# bontor_mbed_lowpan_rev_f.net
KiCad netlist of a schematic drawn in EAGLE
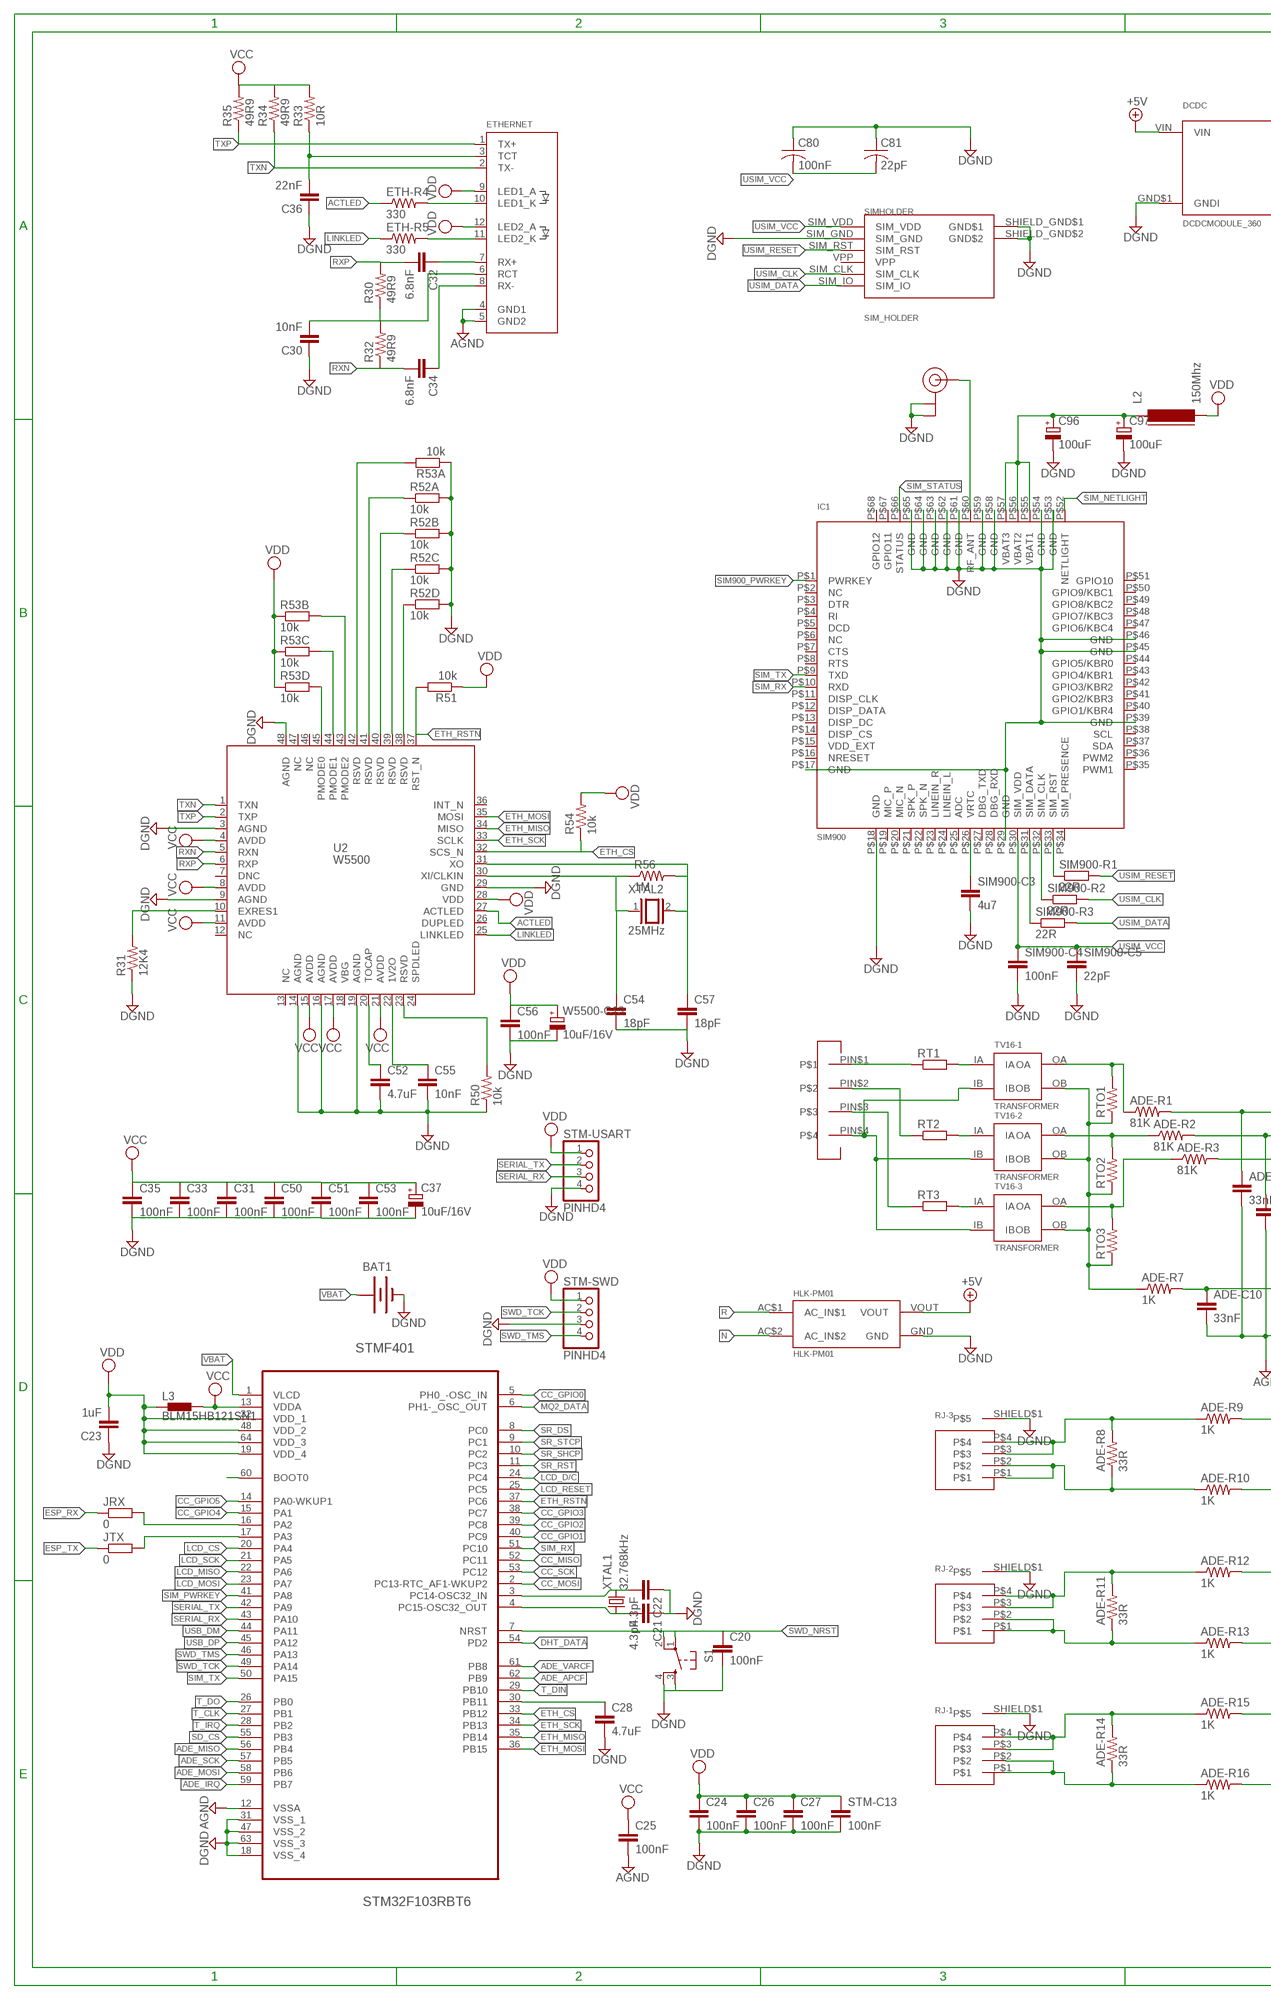
[diagram p0: schematic, sheet 1, part 1 of 2]
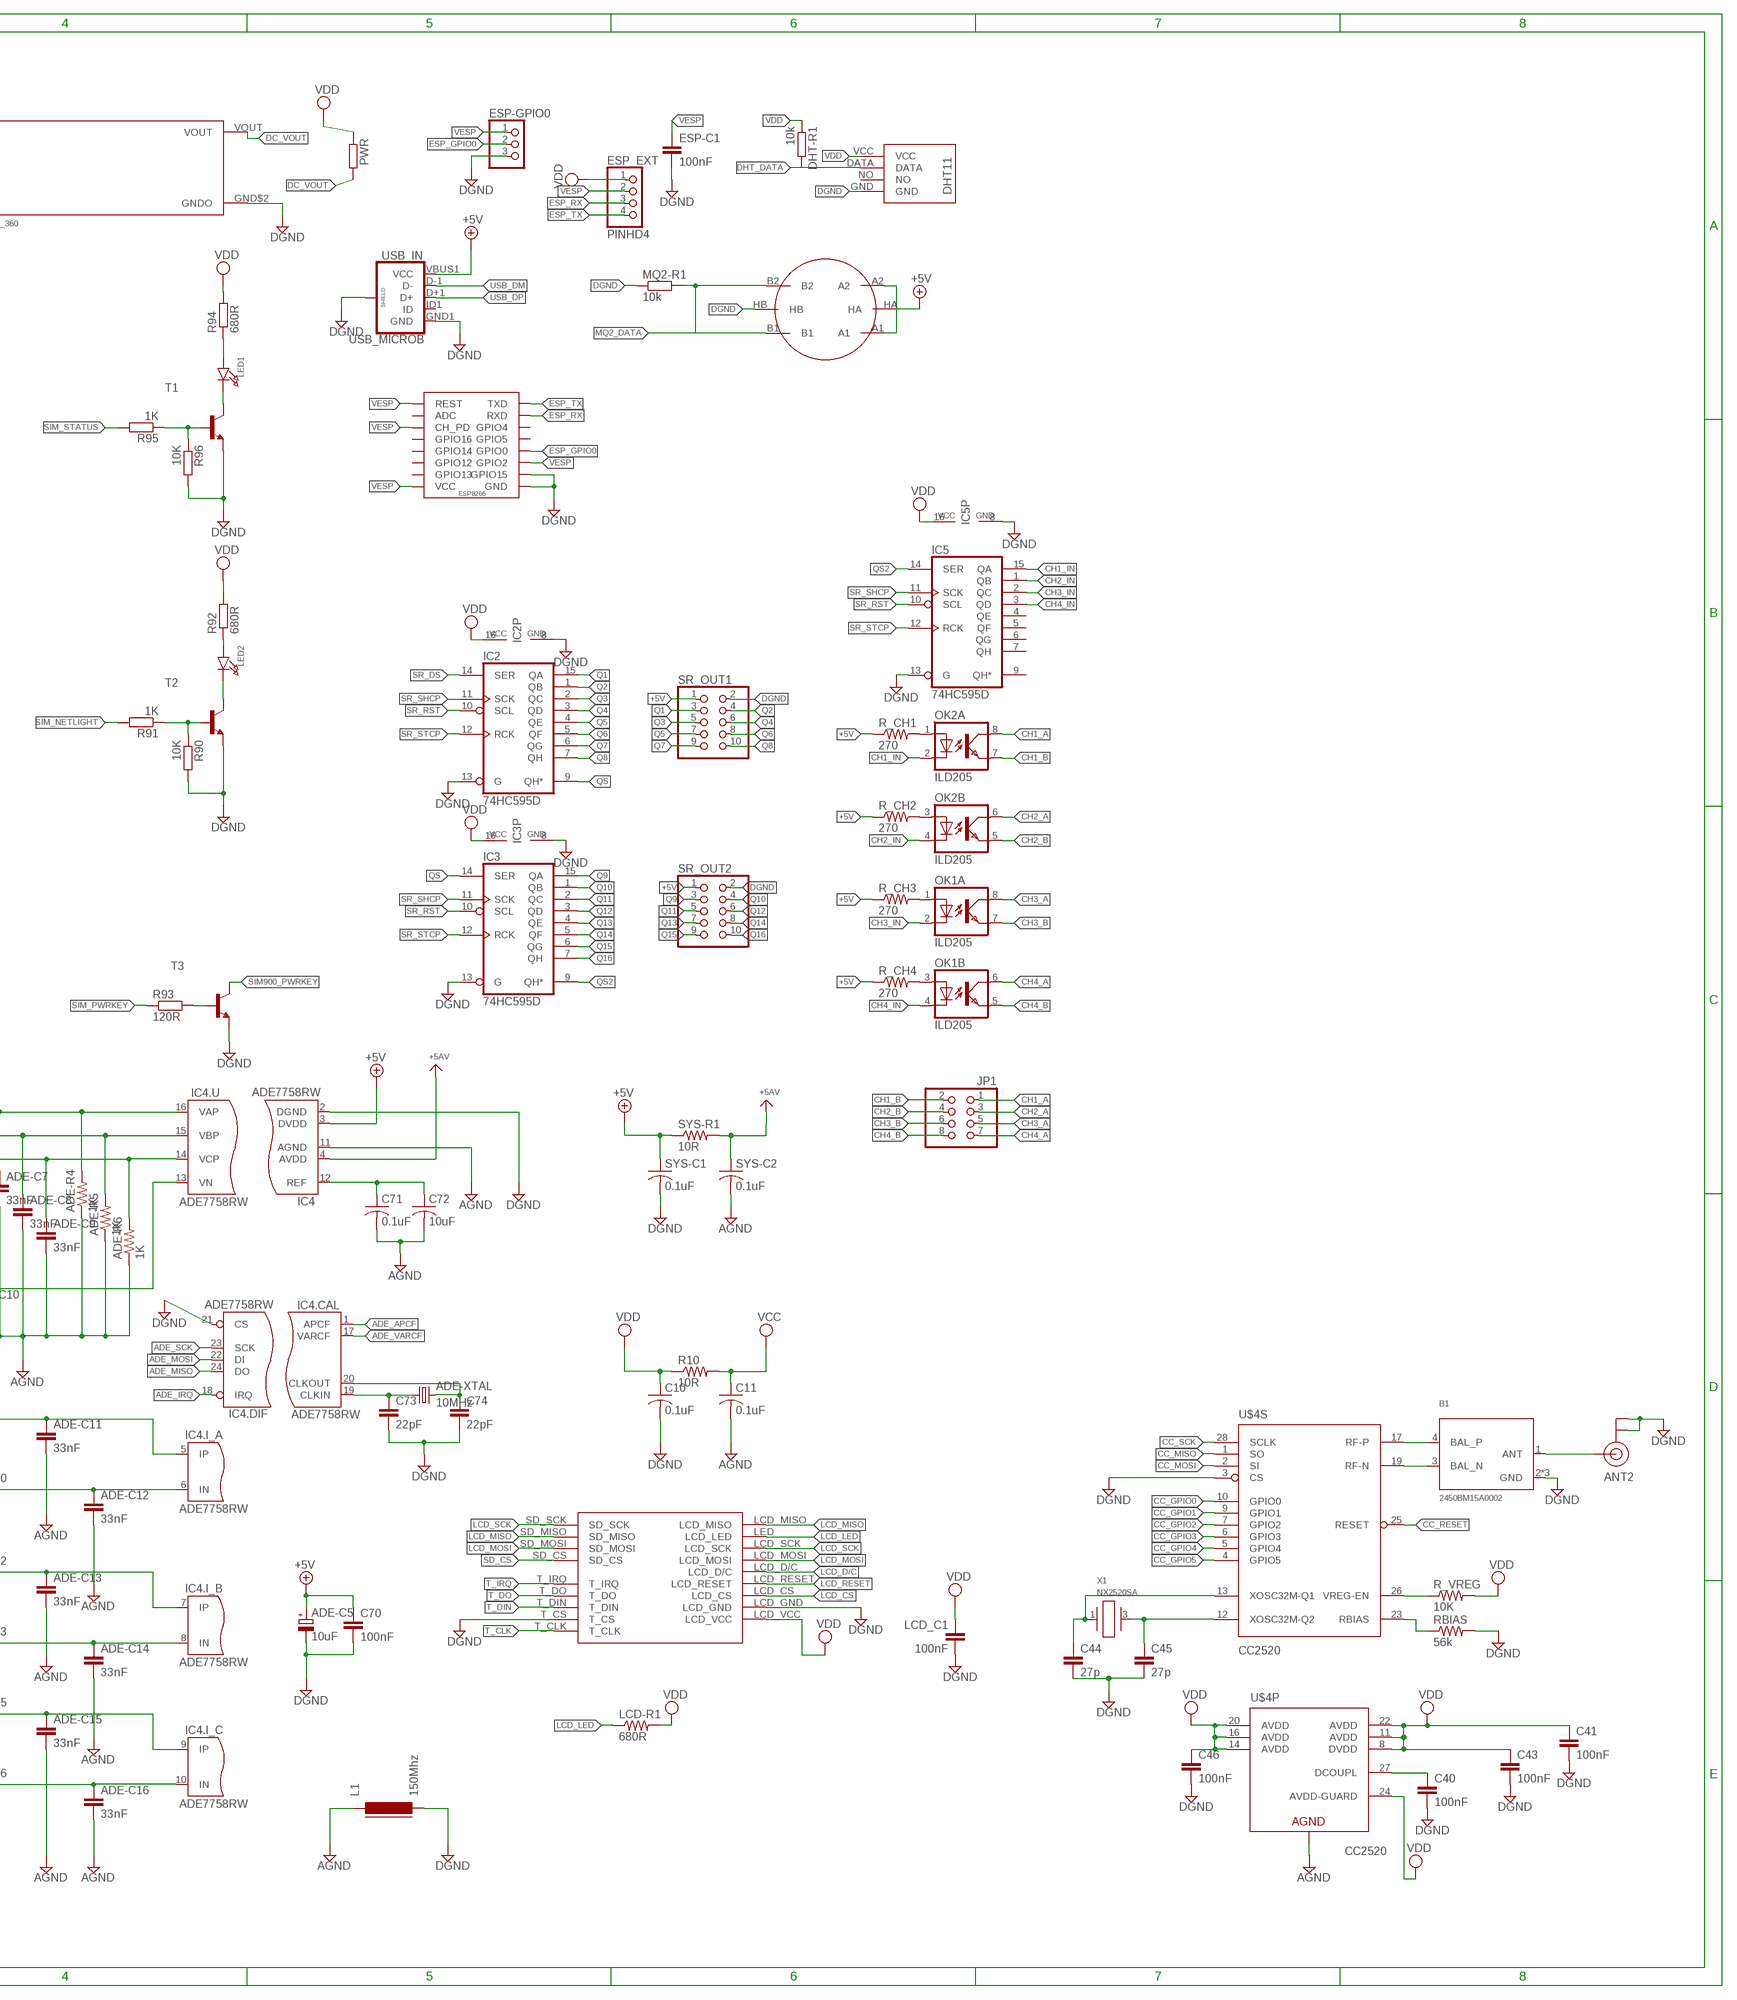
[diagram p1: schematic, sheet 1, part 2 of 2]

(export (version "E")
  (design (tool "Eeschema 10.0.6"))
  (components
    (comp (ref "ADE-C5")
      (value "10uF")
      (footprint "eagle-import:153CLV-0605")
      (libsource (lib "eagle-import") (part "CPOL-EU153CLV-0605"))
    )
    (comp (ref "ADE-C7")
      (value "33nF")
      (footprint "eagle-import:0603-CAP")
      (libsource (lib "eagle-import") (part "CAP0603-CAP"))
    )
    (comp (ref "ADE-C8")
      (value "33nF")
      (footprint "eagle-import:0603-CAP")
      (libsource (lib "eagle-import") (part "CAP0603-CAP"))
    )
    (comp (ref "ADE-C9")
      (value "33nF")
      (footprint "eagle-import:0603-CAP")
      (libsource (lib "eagle-import") (part "CAP0603-CAP"))
    )
    (comp (ref "ADE-C10")
      (value "33nF")
      (footprint "eagle-import:0603-CAP")
      (libsource (lib "eagle-import") (part "CAP0603-CAP"))
    )
    (comp (ref "ADE-C11")
      (value "33nF")
      (footprint "eagle-import:0402-CAP")
      (libsource (lib "eagle-import") (part "CAP0402-CAP"))
    )
    (comp (ref "ADE-C12")
      (value "33nF")
      (footprint "eagle-import:0402-CAP")
      (libsource (lib "eagle-import") (part "CAP0402-CAP"))
    )
    (comp (ref "ADE-C13")
      (value "33nF")
      (footprint "eagle-import:0402-CAP")
      (libsource (lib "eagle-import") (part "CAP0402-CAP"))
    )
    (comp (ref "ADE-C14")
      (value "33nF")
      (footprint "eagle-import:0402-CAP")
      (libsource (lib "eagle-import") (part "CAP0402-CAP"))
    )
    (comp (ref "ADE-C15")
      (value "33nF")
      (footprint "eagle-import:0402-CAP")
      (libsource (lib "eagle-import") (part "CAP0402-CAP"))
    )
    (comp (ref "ADE-C16")
      (value "33nF")
      (footprint "eagle-import:0402-CAP")
      (libsource (lib "eagle-import") (part "CAP0402-CAP"))
    )
    (comp (ref "ADE-R1")
      (value "81K")
      (footprint "eagle-import:0603-RES")
      (libsource (lib "eagle-import") (part "RESISTOR0603-RES"))
    )
    (comp (ref "ADE-R2")
      (value "81K")
      (footprint "eagle-import:0603-RES")
      (libsource (lib "eagle-import") (part "RESISTOR0603-RES"))
    )
    (comp (ref "ADE-R3")
      (value "81K")
      (footprint "eagle-import:0603-RES")
      (libsource (lib "eagle-import") (part "RESISTOR0603-RES"))
    )
    (comp (ref "ADE-R4")
      (value "1K")
      (footprint "eagle-import:0603-RES")
      (libsource (lib "eagle-import") (part "RESISTOR0603-RES"))
    )
    (comp (ref "ADE-R5")
      (value "1K")
      (footprint "eagle-import:0603-RES")
      (libsource (lib "eagle-import") (part "RESISTOR0603-RES"))
    )
    (comp (ref "ADE-R6")
      (value "1K")
      (footprint "eagle-import:0603-RES")
      (libsource (lib "eagle-import") (part "RESISTOR0603-RES"))
    )
    (comp (ref "ADE-R7")
      (value "1K")
      (footprint "eagle-import:0603-RES")
      (libsource (lib "eagle-import") (part "RESISTOR0603-RES"))
    )
    (comp (ref "ADE-R8")
      (value "33R")
      (footprint "eagle-import:0402-RES")
      (libsource (lib "eagle-import") (part "RESISTOR0402-RES"))
    )
    (comp (ref "ADE-R9")
      (value "1K")
      (footprint "eagle-import:0402-RES")
      (libsource (lib "eagle-import") (part "RESISTOR0402-RES"))
    )
    (comp (ref "ADE-R10")
      (value "1K")
      (footprint "eagle-import:0402-RES")
      (libsource (lib "eagle-import") (part "RESISTOR0402-RES"))
    )
    (comp (ref "ADE-R11")
      (value "33R")
      (footprint "eagle-import:0402-RES")
      (libsource (lib "eagle-import") (part "RESISTOR0402-RES"))
    )
    (comp (ref "ADE-R12")
      (value "1K")
      (footprint "eagle-import:0402-RES")
      (libsource (lib "eagle-import") (part "RESISTOR0402-RES"))
    )
    (comp (ref "ADE-R13")
      (value "1K")
      (footprint "eagle-import:0402-RES")
      (libsource (lib "eagle-import") (part "RESISTOR0402-RES"))
    )
    (comp (ref "ADE-R14")
      (value "33R")
      (footprint "eagle-import:0402-RES")
      (libsource (lib "eagle-import") (part "RESISTOR0402-RES"))
    )
    (comp (ref "ADE-R15")
      (value "1K")
      (footprint "eagle-import:0402-RES")
      (libsource (lib "eagle-import") (part "RESISTOR0402-RES"))
    )
    (comp (ref "ADE-R16")
      (value "1K")
      (footprint "eagle-import:0402-RES")
      (libsource (lib "eagle-import") (part "RESISTOR0402-RES"))
    )
    (comp (ref "ADE-XTAL")
      (value "10MHz")
      (footprint "eagle-import:HC49US")
      (libsource (lib "eagle-import") (part "CRYSTALHC49US"))
    )
    (comp (ref "ANT1")
      (value "U.FL")
      (footprint "eagle-import:U.FL")
      (libsource (lib "eagle-import") (part "U.FL"))
    )
    (comp (ref "ANT2")
      (value "U.FL")
      (footprint "eagle-import:U.FL")
      (libsource (lib "eagle-import") (part "SparkFun-Connectors_U.FL"))
    )
    (comp (ref "B1")
      (value "2450BM15A0002")
      (footprint "eagle-import:2450BM")
      (libsource (lib "eagle-import") (part "2450BM15A0002"))
    )
    (comp (ref "BAT1")
      (value "BATTERY12MM")
      (footprint "eagle-import:BATTCON_12MM")
      (libsource (lib "eagle-import") (part "BATTERY12MM"))
    )
    (comp (ref "C10")
      (value "0.1uF")
      (footprint "eagle-import:C0603@1")
      (libsource (lib "eagle-import") (part "C-USC0603"))
    )
    (comp (ref "C11")
      (value "0.1uF")
      (footprint "eagle-import:C0603@1")
      (libsource (lib "eagle-import") (part "C-USC0603"))
    )
    (comp (ref "C20")
      (value "100nF")
      (footprint "eagle-import:C0603")
      (libsource (lib "eagle-import") (part "C-EUC0603"))
    )
    (comp (ref "C21")
      (value "4.3pF")
      (footprint "eagle-import:C0603")
      (libsource (lib "eagle-import") (part "C-EUC0603"))
    )
    (comp (ref "C22")
      (value "4.3pF")
      (footprint "eagle-import:C0603")
      (libsource (lib "eagle-import") (part "C-EUC0603"))
    )
    (comp (ref "C23")
      (value "1uF")
      (footprint "eagle-import:C0603")
      (libsource (lib "eagle-import") (part "C-EUC0603"))
    )
    (comp (ref "C24")
      (value "100nF")
      (footprint "eagle-import:C0603")
      (libsource (lib "eagle-import") (part "C-EUC0603"))
    )
    (comp (ref "C25")
      (value "100nF")
      (footprint "eagle-import:C0603")
      (libsource (lib "eagle-import") (part "C-EUC0603"))
    )
    (comp (ref "C26")
      (value "100nF")
      (footprint "eagle-import:C0603")
      (libsource (lib "eagle-import") (part "C-EUC0603"))
    )
    (comp (ref "C27")
      (value "100nF")
      (footprint "eagle-import:C0402")
      (libsource (lib "eagle-import") (part "C-EUC0402"))
    )
    (comp (ref "C28")
      (value "4.7uF")
      (footprint "eagle-import:C0603")
      (libsource (lib "eagle-import") (part "C-EUC0603"))
    )
    (comp (ref "C30")
      (value "10nF")
      (footprint "eagle-import:C0603")
      (libsource (lib "eagle-import") (part "C-EUC0603"))
    )
    (comp (ref "C31")
      (value "100nF")
      (footprint "eagle-import:C0603")
      (libsource (lib "eagle-import") (part "C-EUC0603"))
    )
    (comp (ref "C32")
      (value "6.8nF")
      (footprint "eagle-import:C0603")
      (libsource (lib "eagle-import") (part "C-EUC0603"))
    )
    (comp (ref "C33")
      (value "100nF")
      (footprint "eagle-import:C0603")
      (libsource (lib "eagle-import") (part "C-EUC0603"))
    )
    (comp (ref "C34")
      (value "6.8nF")
      (footprint "eagle-import:C0603")
      (libsource (lib "eagle-import") (part "C-EUC0603"))
    )
    (comp (ref "C35")
      (value "100nF")
      (footprint "eagle-import:C0603")
      (libsource (lib "eagle-import") (part "C-EUC0603"))
    )
    (comp (ref "C36")
      (value "22nF")
      (footprint "eagle-import:C0603")
      (libsource (lib "eagle-import") (part "C-EUC0603"))
    )
    (comp (ref "C37")
      (value "10uF/16V")
      (footprint "eagle-import:153CLV-0605")
      (libsource (lib "eagle-import") (part "CPOL-EU153CLV-0605"))
    )
    (comp (ref "C40")
      (value "100nF")
      (footprint "eagle-import:C0402")
      (libsource (lib "eagle-import") (part "C-EUC0402"))
    )
    (comp (ref "C41")
      (value "100nF")
      (footprint "eagle-import:C0402")
      (libsource (lib "eagle-import") (part "C-EUC0402"))
    )
    (comp (ref "C43")
      (value "100nF")
      (footprint "eagle-import:C0402")
      (libsource (lib "eagle-import") (part "C-EUC0402"))
    )
    (comp (ref "C44")
      (value "27p")
      (footprint "eagle-import:C0201")
      (libsource (lib "eagle-import") (part "C-EUC0201"))
    )
    (comp (ref "C45")
      (value "27p")
      (footprint "eagle-import:C0201")
      (libsource (lib "eagle-import") (part "C-EUC0201"))
    )
    (comp (ref "C46")
      (value "100nF")
      (footprint "eagle-import:C0402")
      (libsource (lib "eagle-import") (part "C-EUC0402"))
    )
    (comp (ref "C50")
      (value "100nF")
      (footprint "eagle-import:C0603")
      (libsource (lib "eagle-import") (part "C-EUC0603"))
    )
    (comp (ref "C51")
      (value "100nF")
      (footprint "eagle-import:C0603")
      (libsource (lib "eagle-import") (part "C-EUC0603"))
    )
    (comp (ref "C52")
      (value "4.7uF")
      (footprint "eagle-import:C0603")
      (libsource (lib "eagle-import") (part "C-EUC0603"))
    )
    (comp (ref "C53")
      (value "100nF")
      (footprint "eagle-import:C0603")
      (libsource (lib "eagle-import") (part "C-EUC0603"))
    )
    (comp (ref "C54")
      (value "18pF")
      (footprint "eagle-import:C0603")
      (libsource (lib "eagle-import") (part "C-EUC0603"))
    )
    (comp (ref "C55")
      (value "10nF")
      (footprint "eagle-import:C0603")
      (libsource (lib "eagle-import") (part "C-EUC0603"))
    )
    (comp (ref "C56")
      (value "100nF")
      (footprint "eagle-import:C0603")
      (libsource (lib "eagle-import") (part "C-EUC0603"))
    )
    (comp (ref "C57")
      (value "18pF")
      (footprint "eagle-import:C0603")
      (libsource (lib "eagle-import") (part "C-EUC0603"))
    )
    (comp (ref "C70")
      (value "100nF")
      (footprint "eagle-import:C0603")
      (libsource (lib "eagle-import") (part "C-EUC0603"))
    )
    (comp (ref "C71")
      (value "0.1uF")
      (footprint "eagle-import:C0603@1")
      (libsource (lib "eagle-import") (part "C-USC0603"))
    )
    (comp (ref "C72")
      (value "10uF")
      (footprint "eagle-import:C0805K")
      (libsource (lib "eagle-import") (part "C-USC0805K"))
    )
    (comp (ref "C73")
      (value "22pF")
      (footprint "eagle-import:C0603")
      (libsource (lib "eagle-import") (part "C-EUC0603"))
    )
    (comp (ref "C74")
      (value "22pF")
      (footprint "eagle-import:C0603")
      (libsource (lib "eagle-import") (part "C-EUC0603"))
    )
    (comp (ref "C80")
      (value "100nF")
      (footprint "eagle-import:C0603K")
      (libsource (lib "eagle-import") (part "C-USC0603K"))
    )
    (comp (ref "C81")
      (value "22pF")
      (footprint "eagle-import:C0603K")
      (libsource (lib "eagle-import") (part "C-USC0603K"))
    )
    (comp (ref "C96")
      (value "100uF")
      (footprint "eagle-import:153CLV-0605")
      (libsource (lib "eagle-import") (part "CPOL-EU153CLV-0605"))
    )
    (comp (ref "C97")
      (value "100uF")
      (footprint "eagle-import:153CLV-0605")
      (libsource (lib "eagle-import") (part "CPOL-EU153CLV-0605"))
    )
    (comp (ref "DCDC")
      (value "DCDCMODULE_360")
      (footprint "eagle-import:DCDCMODULE-360")
      (libsource (lib "eagle-import") (part "DCDCMODULE_360"))
    )
    (comp (ref "DHT-R1")
      (value "10k")
      (footprint "eagle-import:R0603")
      (libsource (lib "eagle-import") (part "resistor_R-EU_R0603"))
    )
    (comp (ref "ESP")
      (value "ESP")
      (footprint "eagle-import:WI12")
      (libsource (lib "eagle-import") (part "ESP8266WI12"))
    )
    (comp (ref "ESP-C1")
      (value "100nF")
      (footprint "eagle-import:C0603")
      (libsource (lib "eagle-import") (part "C-EUC0603"))
    )
    (comp (ref "ESP-GPIO0")
      (value "PINHD-1X3")
      (footprint "eagle-import:1X03")
      (libsource (lib "eagle-import") (part "PINHD-1X3"))
    )
    (comp (ref "ESP_EXT")
      (value "PINHD4")
      (footprint "eagle-import:PINHD4")
      (libsource (lib "eagle-import") (part "PINHD4"))
    )
    (comp (ref "ETH-R4")
      (value "330")
      (footprint "eagle-import:R0603")
      (libsource (lib "eagle-import") (part "resistor_R-US_R0603"))
    )
    (comp (ref "ETH-R5")
      (value "330")
      (footprint "eagle-import:R0603")
      (libsource (lib "eagle-import") (part "resistor_R-US_R0603"))
    )
    (comp (ref "ETHERNET")
      (value "RJ45J0026D21BNL")
      (footprint "eagle-import:RJ45_PULSEJACK")
      (libsource (lib "eagle-import") (part "RJ45J0026D21BNL"))
    )
    (comp (ref "HLK-PM01")
      (value "HLK-PM01")
      (footprint "eagle-import:HLK-PM01")
      (libsource (lib "eagle-import") (part "HLK-PM01"))
    )
    (comp (ref "IC1")
      (value "SIM900")
      (footprint "eagle-import:SIM900_SMT")
      (libsource (lib "eagle-import") (part "GSM_SIM900_LITERAL"))
    )
    (comp (ref "IC2")
      (value "74HC595D")
      (footprint "eagle-import:SO16")
      (libsource (lib "eagle-import") (part "74595DHC"))
    )
    (comp (ref "IC3")
      (value "74HC595D")
      (footprint "eagle-import:SO16")
      (libsource (lib "eagle-import") (part "74595DHC"))
    )
    (comp (ref "IC4")
      (value "ADE7758RW")
      (footprint "eagle-import:SOIC24")
      (libsource (lib "eagle-import") (part "ADE7758RW"))
    )
    (comp (ref "IC5")
      (value "74HC595D")
      (footprint "eagle-import:SO16")
      (libsource (lib "eagle-import") (part "74595DHC"))
    )
    (comp (ref "JP1")
      (value "PINHD-2X4")
      (footprint "eagle-import:2X04")
      (libsource (lib "eagle-import") (part "PINHD-2X4"))
    )
    (comp (ref "JRX")
      (value "0")
      (footprint "eagle-import:R0201")
      (libsource (lib "eagle-import") (part "R-EU_R0201"))
    )
    (comp (ref "JTX")
      (value "0")
      (footprint "eagle-import:R0201")
      (libsource (lib "eagle-import") (part "R-EU_R0201"))
    )
    (comp (ref "L1")
      (value "150Mhz")
      (footprint "eagle-import:FB805")
      (libsource (lib "eagle-import") (part "FERRITE-0805"))
    )
    (comp (ref "L2")
      (value "150Mhz")
      (footprint "eagle-import:FB805")
      (libsource (lib "eagle-import") (part "FERRITE-0805"))
    )
    (comp (ref "L3")
      (value "BLM15HB121SN1")
      (footprint "eagle-import:0402")
      (libsource (lib "eagle-import") (part "BLM15HB121SN1"))
    )
    (comp (ref "LCD-R1")
      (value "680R")
      (footprint "eagle-import:0603-RES")
      (libsource (lib "eagle-import") (part "RESISTOR0603-RES"))
    )
    (comp (ref "LCD14")
      (value "LCD_2.4")
      (footprint "eagle-import:LCD_TOUCH_2-4")
      (libsource (lib "eagle-import") (part "LCD_2.4"))
    )
    (comp (ref "LCD_C1")
      (value "100nF")
      (footprint "eagle-import:C0603")
      (libsource (lib "eagle-import") (part "C-EUC0603"))
    )
    (comp (ref "LED1")
      (value "LED0805_NOOUTLINE")
      (footprint "eagle-import:CHIPLED_0805_NOOUTLINE")
      (libsource (lib "eagle-import") (part "LED0805_NOOUTLINE"))
    )
    (comp (ref "LED2")
      (value "LED0805_NOOUTLINE")
      (footprint "eagle-import:CHIPLED_0805_NOOUTLINE")
      (libsource (lib "eagle-import") (part "LED0805_NOOUTLINE"))
    )
    (comp (ref "MQ2-R1")
      (value "10k")
      (footprint "eagle-import:R0603")
      (libsource (lib "eagle-import") (part "resistor_R-EU_R0603"))
    )
    (comp (ref "OK1")
      (value "ILD205")
      (footprint "eagle-import:SOIC08")
      (fields (field (name "MF") "VISHAY/TELEFUNKEN") (field (name "MPN") "ILD205T"))
      (libsource (lib "eagle-import") (part "ILD205"))
    )
    (comp (ref "OK2")
      (value "ILD205")
      (footprint "eagle-import:SOIC08")
      (fields (field (name "MF") "VISHAY/TELEFUNKEN") (field (name "MPN") "ILD205T"))
      (libsource (lib "eagle-import") (part "ILD205"))
    )
    (comp (ref "PWR")
      (value "R-EU_R0402")
      (footprint "eagle-import:R0402")
      (libsource (lib "eagle-import") (part "R-EU_R0402"))
    )
    (comp (ref "R10")
      (value "10R")
      (footprint "eagle-import:0603-RES")
      (libsource (lib "eagle-import") (part "RESISTOR0603-RES"))
    )
    (comp (ref "R30")
      (value "49R9")
      (footprint "eagle-import:R0603")
      (libsource (lib "eagle-import") (part "resistor_R-US_R0603"))
    )
    (comp (ref "R31")
      (value "12K4")
      (footprint "eagle-import:R0805")
      (libsource (lib "eagle-import") (part "resistor_R-US_R0805"))
    )
    (comp (ref "R32")
      (value "49R9")
      (footprint "eagle-import:R0603")
      (libsource (lib "eagle-import") (part "resistor_R-US_R0603"))
    )
    (comp (ref "R33")
      (value "10R")
      (footprint "eagle-import:R0603")
      (libsource (lib "eagle-import") (part "resistor_R-US_R0603"))
    )
    (comp (ref "R34")
      (value "49R9")
      (footprint "eagle-import:R0603")
      (libsource (lib "eagle-import") (part "resistor_R-US_R0603"))
    )
    (comp (ref "R35")
      (value "49R9")
      (footprint "eagle-import:R0603")
      (libsource (lib "eagle-import") (part "resistor_R-US_R0603"))
    )
    (comp (ref "R50")
      (value "10k")
      (footprint "eagle-import:R0603")
      (libsource (lib "eagle-import") (part "resistor_R-US_R0603"))
    )
    (comp (ref "R51")
      (value "10k")
      (footprint "eagle-import:R0603")
      (libsource (lib "eagle-import") (part "R-EU_R0603"))
    )
    (comp (ref "R52")
      (value "10k")
      (footprint "eagle-import:RN8P-4R-CRA06S")
      (libsource (lib "eagle-import") (part "RESISTOR_ARRAY_4"))
    )
    (comp (ref "R53")
      (value "10k")
      (footprint "eagle-import:RN8P-4R-CRA06S")
      (libsource (lib "eagle-import") (part "RESISTOR_ARRAY_4"))
    )
    (comp (ref "R54")
      (value "10k")
      (footprint "eagle-import:R0603")
      (libsource (lib "eagle-import") (part "resistor_R-US_R0603"))
    )
    (comp (ref "R56")
      (value "1M")
      (footprint "eagle-import:R0603")
      (libsource (lib "eagle-import") (part "resistor_R-US_R0603"))
    )
    (comp (ref "R90")
      (value "10K")
      (footprint "eagle-import:R0603")
      (libsource (lib "eagle-import") (part "R-EU_R0603"))
    )
    (comp (ref "R91")
      (value "1K")
      (footprint "eagle-import:R0603")
      (libsource (lib "eagle-import") (part "R-EU_R0603"))
    )
    (comp (ref "R92")
      (value "680R")
      (footprint "eagle-import:R0603")
      (libsource (lib "eagle-import") (part "R-EU_R0603"))
    )
    (comp (ref "R93")
      (value "120R")
      (footprint "eagle-import:R0603")
      (libsource (lib "eagle-import") (part "resistor_R-EU_R0603"))
    )
    (comp (ref "R94")
      (value "680R")
      (footprint "eagle-import:R0603")
      (libsource (lib "eagle-import") (part "R-EU_R0603"))
    )
    (comp (ref "R95")
      (value "1K")
      (footprint "eagle-import:R0603")
      (libsource (lib "eagle-import") (part "R-EU_R0603"))
    )
    (comp (ref "R96")
      (value "10K")
      (footprint "eagle-import:R0603")
      (libsource (lib "eagle-import") (part "R-EU_R0603"))
    )
    (comp (ref "RBIAS")
      (value "56k")
      (footprint "eagle-import:0402-RES")
      (libsource (lib "eagle-import") (part "RESISTOR0402-RES"))
    )
    (comp (ref "RJ-1")
      (value "RJ11-4P-V")
      (footprint "eagle-import:RJ11-4P-V")
      (libsource (lib "eagle-import") (part "RJ11-4P-V"))
    )
    (comp (ref "RJ-2")
      (value "RJ11-4P-V")
      (footprint "eagle-import:RJ11-4P-V")
      (libsource (lib "eagle-import") (part "RJ11-4P-V"))
    )
    (comp (ref "RJ-3")
      (value "RJ11-4P-V")
      (footprint "eagle-import:RJ11-4P-V")
      (libsource (lib "eagle-import") (part "RJ11-4P-V"))
    )
    (comp (ref "RT1")
      (value "R-EU_0309/V")
      (footprint "eagle-import:0309V")
      (libsource (lib "eagle-import") (part "R-EU_0309/V"))
    )
    (comp (ref "RT2")
      (value "R-EU_0309/V")
      (footprint "eagle-import:0309V")
      (libsource (lib "eagle-import") (part "R-EU_0309/V"))
    )
    (comp (ref "RT3")
      (value "R-EU_0309/V")
      (footprint "eagle-import:0309V")
      (libsource (lib "eagle-import") (part "R-EU_0309/V"))
    )
    (comp (ref "RTO1")
      (value "R-US_0309_12")
      (footprint "eagle-import:0309_12")
      (libsource (lib "eagle-import") (part "R-US_0309_12"))
    )
    (comp (ref "RTO2")
      (value "R-US_0309_12")
      (footprint "eagle-import:0309_12")
      (libsource (lib "eagle-import") (part "R-US_0309_12"))
    )
    (comp (ref "RTO3")
      (value "R-US_0309_12")
      (footprint "eagle-import:0309_12")
      (libsource (lib "eagle-import") (part "R-US_0309_12"))
    )
    (comp (ref "R_CH1")
      (value "270")
      (footprint "eagle-import:0603-RES")
      (libsource (lib "eagle-import") (part "RESISTOR0603-RES"))
    )
    (comp (ref "R_CH2")
      (value "270")
      (footprint "eagle-import:0603-RES")
      (libsource (lib "eagle-import") (part "RESISTOR0603-RES"))
    )
    (comp (ref "R_CH3")
      (value "270")
      (footprint "eagle-import:0603-RES")
      (libsource (lib "eagle-import") (part "RESISTOR0603-RES"))
    )
    (comp (ref "R_CH4")
      (value "270")
      (footprint "eagle-import:0603-RES")
      (libsource (lib "eagle-import") (part "RESISTOR0603-RES"))
    )
    (comp (ref "R_VREG")
      (value "10K")
      (footprint "eagle-import:0402-RES")
      (libsource (lib "eagle-import") (part "RESISTOR0402-RES"))
    )
    (comp (ref "S1")
      (value "TAC_SWITCHPTH")
      (footprint "eagle-import:TACTILE-PTH")
      (libsource (lib "eagle-import") (part "TAC_SWITCHPTH"))
    )
    (comp (ref "SENSOR-MQ2")
      (value "METHANE_SENSOR")
      (footprint "eagle-import:MQ-3")
      (libsource (lib "eagle-import") (part "METHANE_SENSOR"))
    )
    (comp (ref "SIM900-C3")
      (value "4u7")
      (footprint "eagle-import:C0603")
      (libsource (lib "eagle-import") (part "C-EUC0603"))
    )
    (comp (ref "SIM900-C4")
      (value "100nF")
      (footprint "eagle-import:C0603")
      (libsource (lib "eagle-import") (part "C-EUC0603"))
    )
    (comp (ref "SIM900-C5")
      (value "22pF")
      (footprint "eagle-import:C0603")
      (libsource (lib "eagle-import") (part "C-EUC0603"))
    )
    (comp (ref "SIM900-R1")
      (value "22R")
      (footprint "eagle-import:R0603")
      (libsource (lib "eagle-import") (part "R-EU_R0603"))
    )
    (comp (ref "SIM900-R2")
      (value "22R")
      (footprint "eagle-import:R0603")
      (libsource (lib "eagle-import") (part "R-EU_R0603"))
    )
    (comp (ref "SIM900-R3")
      (value "22R")
      (footprint "eagle-import:R0603")
      (libsource (lib "eagle-import") (part "R-EU_R0603"))
    )
    (comp (ref "SIMHOLDER")
      (value "SIM_HOLDER")
      (footprint "eagle-import:SIMHOLDER-PUSHPUSH")
      (libsource (lib "eagle-import") (part "SIM_HOLDER"))
    )
    (comp (ref "SR_OUT1")
      (value "PINHD-2X5")
      (footprint "eagle-import:2X05")
      (libsource (lib "eagle-import") (part "PINHD-2X5"))
    )
    (comp (ref "SR_OUT2")
      (value "PINHD-2X5")
      (footprint "eagle-import:2X05")
      (libsource (lib "eagle-import") (part "PINHD-2X5"))
    )
    (comp (ref "STM-C13")
      (value "100nF")
      (footprint "eagle-import:C0603")
      (libsource (lib "eagle-import") (part "C-EUC0603"))
    )
    (comp (ref "STM-SWD")
      (value "PINHD4")
      (footprint "eagle-import:PINHD4")
      (libsource (lib "eagle-import") (part "PINHD4"))
    )
    (comp (ref "STM-USART")
      (value "PINHD4")
      (footprint "eagle-import:PINHD4")
      (libsource (lib "eagle-import") (part "PINHD4"))
    )
    (comp (ref "STMF401")
      (value "STM32F103RBT6")
      (footprint "eagle-import:QFP50P1200X1200X160-64N")
      (fields (field (name "MPN") "STM32L152RBT6"))
      (libsource (lib "eagle-import") (part "STM32L152RBT6"))
    )
    (comp (ref "SYS-C1")
      (value "0.1uF")
      (footprint "eagle-import:C0603@1")
      (libsource (lib "eagle-import") (part "C-USC0603"))
    )
    (comp (ref "SYS-C2")
      (value "0.1uF")
      (footprint "eagle-import:C0603@1")
      (libsource (lib "eagle-import") (part "C-USC0603"))
    )
    (comp (ref "SYS-R1")
      (value "10R")
      (footprint "eagle-import:0603-RES")
      (libsource (lib "eagle-import") (part "RESISTOR0603-RES"))
    )
    (comp (ref "T1")
      (value "MMBT2222ALT1-NPN-SOT23-BEC")
      (footprint "eagle-import:SOT23-BEC")
      (libsource (lib "eagle-import") (part "-NPN-SOT23-BECMMBT2222ALT1"))
    )
    (comp (ref "T2")
      (value "MMBT2222ALT1-NPN-SOT23-BEC")
      (footprint "eagle-import:SOT23-BEC")
      (libsource (lib "eagle-import") (part "-NPN-SOT23-BECMMBT2222ALT1"))
    )
    (comp (ref "T3")
      (value "MMBT2222ALT1-NPN-SOT23-BEC")
      (footprint "eagle-import:SOT23-BEC")
      (libsource (lib "eagle-import") (part "transistor-neu-to92_-NPN-SOT23-BECMMBT2222ALT1"))
    )
    (comp (ref "TERM_BLOCK")
      (value "TERMINAL_BLOCK_TW")
      (footprint "eagle-import:TERMINAL-TWO-WAY")
      (libsource (lib "eagle-import") (part "TERMINAL_BLOCK_TW"))
    )
    (comp (ref "TV16-1")
      (value "TRANSFORMER")
      (footprint "eagle-import:TV16")
      (libsource (lib "eagle-import") (part "TRANSFORMER"))
    )
    (comp (ref "TV16-2")
      (value "TRANSFORMER")
      (footprint "eagle-import:TV16")
      (libsource (lib "eagle-import") (part "TRANSFORMER"))
    )
    (comp (ref "TV16-3")
      (value "TRANSFORMER")
      (footprint "eagle-import:TV16")
      (libsource (lib "eagle-import") (part "TRANSFORMER"))
    )
    (comp (ref "U$4")
      (value "CC2520")
      (footprint "eagle-import:QFN50P500X500X100-29N")
      (libsource (lib "eagle-import") (part "CC2520"))
    )
    (comp (ref "U$17")
      (value "DHT11")
      (footprint "eagle-import:DHT11")
      (libsource (lib "eagle-import") (part "DHT11"))
    )
    (comp (ref "U2")
      (value "W5500")
      (footprint "eagle-import:W5500")
      (libsource (lib "eagle-import") (part "W5500"))
    )
    (comp (ref "USB_IN")
      (value "USB_MICROB")
      (footprint "eagle-import:USB-B-MICRO-SMD_V03")
      (libsource (lib "eagle-import") (part "USB_MICROB_PLUGCONN-11752"))
    )
    (comp (ref "W5500-C13")
      (value "10uF/16V")
      (footprint "eagle-import:153CLV-0605")
      (libsource (lib "eagle-import") (part "CPOL-EU153CLV-0605"))
    )
    (comp (ref "X1")
      (value "NX2520SA")
      (footprint "eagle-import:NX2520SA")
      (libsource (lib "eagle-import") (part "NX2520SA"))
    )
    (comp (ref "XTAL1")
      (value "32.768kHz")
      (footprint "eagle-import:TC26H")
      (libsource (lib "eagle-import") (part "CRYSTALTC26H"))
    )
    (comp (ref "XTAL2")
      (value "25MHz")
      (footprint "eagle-import:QS")
      (libsource (lib "eagle-import") (part "XTAL/S"))
    )
  )
  (nets
    (net (code "1") (name "+5AV") (class "Default")
      (node (ref "IC4") (pin "4") (pinfunction "AVDD_4") (pintype "power_in"))
      (node (ref "SYS-C2") (pin "1") (pinfunction "1_1") (pintype "passive"))
      (node (ref "SYS-R1") (pin "2") (pinfunction "2_2") (pintype "passive"))
    )
    (net (code "2") (name "+5V") (class "Default")
      (node (ref "ADE-C5") (pin "+") (pinfunction "+_+") (pintype "passive"))
      (node (ref "C70") (pin "1") (pinfunction "1_1") (pintype "passive"))
      (node (ref "DCDC") (pin "VIN") (pinfunction "VIN_VIN") (pintype "bidirectional"))
      (node (ref "HLK-PM01") (pin "VOUT") (pinfunction "VOUT_VOUT") (pintype "bidirectional"))
      (node (ref "IC4") (pin "3") (pinfunction "DVDD_3") (pintype "power_in"))
      (node (ref "R_CH1") (pin "1") (pinfunction "1_1") (pintype "passive"))
      (node (ref "R_CH2") (pin "1") (pinfunction "1_1") (pintype "passive"))
      (node (ref "R_CH3") (pin "1") (pinfunction "1_1") (pintype "passive"))
      (node (ref "R_CH4") (pin "1") (pinfunction "1_1") (pintype "passive"))
      (node (ref "SENSOR-MQ2") (pin "A1") (pinfunction "A1_A1") (pintype "bidirectional"))
      (node (ref "SENSOR-MQ2") (pin "A2") (pinfunction "A2_A2") (pintype "bidirectional"))
      (node (ref "SENSOR-MQ2") (pin "HA") (pinfunction "HA_HA") (pintype "bidirectional"))
      (node (ref "SR_OUT1") (pin "1") (pinfunction "1_1") (pintype "passive"))
      (node (ref "SR_OUT2") (pin "1") (pinfunction "1_1") (pintype "passive"))
      (node (ref "SYS-C1") (pin "1") (pinfunction "1_1") (pintype "passive"))
      (node (ref "SYS-R1") (pin "1") (pinfunction "1_1") (pintype "passive"))
      (node (ref "USB_IN") (pin "VBUS1") (pinfunction "VCC_VBUS1") (pintype "bidirectional"))
    )
    (net (code "3") (name "/GPIO11") (class "Default")
      (node (ref "IC1") (pin "P$67") (pinfunction "GPIO11_P$67") (pintype "power_in"))
    )
    (net (code "4") (name "/GPIO12") (class "Default")
      (node (ref "IC1") (pin "P$68") (pinfunction "GPIO12_P$68") (pintype "power_in"))
    )
    (net (code "5") (name "ACTLED") (class "Default")
      (node (ref "ETH-R4") (pin "1") (pinfunction "1_1") (pintype "passive"))
      (node (ref "U2") (pin "27") (pinfunction "ACTLED_27") (pintype "passive"))
    )
    (net (code "6") (name "ADE_APCF") (class "Default")
      (node (ref "IC4") (pin "1") (pinfunction "APCF_1") (pintype "output"))
      (node (ref "STMF401") (pin "62") (pinfunction "PB9_62") (pintype "bidirectional"))
    )
    (net (code "7") (name "ADE_IRQ") (class "Default")
      (node (ref "IC4") (pin "18") (pinfunction "IRQ_18") (pintype "output"))
      (node (ref "STMF401") (pin "59") (pinfunction "PB7_59") (pintype "bidirectional"))
    )
    (net (code "8") (name "ADE_MISO") (class "Default")
      (node (ref "IC4") (pin "24") (pinfunction "DO_24") (pintype "output"))
      (node (ref "STMF401") (pin "56") (pinfunction "PB4_56") (pintype "bidirectional"))
    )
    (net (code "9") (name "ADE_MOSI") (class "Default")
      (node (ref "IC4") (pin "22") (pinfunction "DI_22") (pintype "input"))
      (node (ref "STMF401") (pin "58") (pinfunction "PB6_58") (pintype "bidirectional"))
    )
    (net (code "10") (name "ADE_SCK") (class "Default")
      (node (ref "IC4") (pin "23") (pinfunction "SCK_23") (pintype "input"))
      (node (ref "STMF401") (pin "57") (pinfunction "PB5_57") (pintype "bidirectional"))
    )
    (net (code "11") (name "ADE_VARCF") (class "Default")
      (node (ref "IC4") (pin "17") (pinfunction "VARCF_17") (pintype "output"))
      (node (ref "STMF401") (pin "61") (pinfunction "PB8_61") (pintype "bidirectional"))
    )
    (net (code "12") (name "AGND") (class "Default")
      (node (ref "ADE-C10") (pin "2") (pinfunction "2_2") (pintype "passive"))
      (node (ref "ADE-C11") (pin "2") (pinfunction "2_2") (pintype "passive"))
      (node (ref "ADE-C12") (pin "2") (pinfunction "2_2") (pintype "passive"))
      (node (ref "ADE-C13") (pin "2") (pinfunction "2_2") (pintype "passive"))
      (node (ref "ADE-C14") (pin "2") (pinfunction "2_2") (pintype "passive"))
      (node (ref "ADE-C15") (pin "2") (pinfunction "2_2") (pintype "passive"))
      (node (ref "ADE-C16") (pin "2") (pinfunction "2_2") (pintype "passive"))
      (node (ref "ADE-C7") (pin "2") (pinfunction "2_2") (pintype "passive"))
      (node (ref "ADE-C8") (pin "2") (pinfunction "2_2") (pintype "passive"))
      (node (ref "ADE-C9") (pin "2") (pinfunction "2_2") (pintype "passive"))
      (node (ref "ADE-R4") (pin "1") (pinfunction "1_1") (pintype "passive"))
      (node (ref "ADE-R5") (pin "1") (pinfunction "1_1") (pintype "passive"))
      (node (ref "ADE-R6") (pin "1") (pinfunction "1_1") (pintype "passive"))
      (node (ref "C11") (pin "2") (pinfunction "2_2") (pintype "passive"))
      (node (ref "C25") (pin "2") (pinfunction "2_2") (pintype "passive"))
      (node (ref "C71") (pin "2") (pinfunction "2_2") (pintype "passive"))
      (node (ref "C72") (pin "2") (pinfunction "2_2") (pintype "passive"))
      (node (ref "ETHERNET") (pin "4") (pinfunction "GND1_4") (pintype "bidirectional"))
      (node (ref "ETHERNET") (pin "5") (pinfunction "GND2_5") (pintype "bidirectional"))
      (node (ref "IC4") (pin "11") (pinfunction "AGND_11") (pintype "power_in"))
      (node (ref "L1") (pin "1") (pinfunction "1_1") (pintype "passive"))
      (node (ref "STMF401") (pin "12") (pinfunction "VSSA_12") (pintype "power_in"))
      (node (ref "SYS-C2") (pin "2") (pinfunction "2_2") (pintype "passive"))
      (node (ref "U$4") (pin "29") (pinfunction "AGND_29") (pintype "power_in"))
    )
    (net (code "13") (name "CC_GPIO0") (class "Default")
      (node (ref "STMF401") (pin "5") (pinfunction "PH0_-OSC_IN_5") (pintype "bidirectional"))
      (node (ref "U$4") (pin "10") (pinfunction "GPIO0_10") (pintype "output"))
    )
    (net (code "14") (name "CC_GPIO1") (class "Default")
      (node (ref "STMF401") (pin "40") (pinfunction "PC9_40") (pintype "bidirectional"))
      (node (ref "U$4") (pin "9") (pinfunction "GPIO1_9") (pintype "output"))
    )
    (net (code "15") (name "CC_GPIO2") (class "Default")
      (node (ref "STMF401") (pin "39") (pinfunction "PC8_39") (pintype "bidirectional"))
      (node (ref "U$4") (pin "7") (pinfunction "GPIO2_7") (pintype "bidirectional"))
    )
    (net (code "16") (name "CC_GPIO3") (class "Default")
      (node (ref "STMF401") (pin "38") (pinfunction "PC7_38") (pintype "bidirectional"))
      (node (ref "U$4") (pin "6") (pinfunction "GPIO3_6") (pintype "bidirectional"))
    )
    (net (code "17") (name "CC_GPIO4") (class "Default")
      (node (ref "STMF401") (pin "15") (pinfunction "PA1_15") (pintype "bidirectional"))
      (node (ref "U$4") (pin "5") (pinfunction "GPIO4_5") (pintype "bidirectional"))
    )
    (net (code "18") (name "CC_GPIO5") (class "Default")
      (node (ref "STMF401") (pin "14") (pinfunction "PA0-WKUP1_14") (pintype "bidirectional"))
      (node (ref "U$4") (pin "4") (pinfunction "GPIO5_4") (pintype "bidirectional"))
    )
    (net (code "19") (name "CC_MISO") (class "Default")
      (node (ref "STMF401") (pin "52") (pinfunction "PC11_52") (pintype "bidirectional"))
      (node (ref "U$4") (pin "1") (pinfunction "SO_1") (pintype "output"))
    )
    (net (code "20") (name "CC_MOSI") (class "Default")
      (node (ref "STMF401") (pin "2") (pinfunction "PC13-RTC_AF1-WKUP2_2") (pintype "bidirectional"))
      (node (ref "U$4") (pin "2") (pinfunction "SI_2") (pintype "input"))
    )
    (net (code "21") (name "CC_RESET") (class "Default")
      (node (ref "U$4") (pin "25") (pinfunction "RESET_25") (pintype "input"))
    )
    (net (code "22") (name "CC_SCK") (class "Default")
      (node (ref "STMF401") (pin "53") (pinfunction "PC12_53") (pintype "bidirectional"))
      (node (ref "U$4") (pin "28") (pinfunction "SCLK_28") (pintype "input"))
    )
    (net (code "23") (name "CH1_A") (class "Default")
      (node (ref "JP1") (pin "1") (pinfunction "1_1") (pintype "passive"))
      (node (ref "OK2") (pin "8") (pinfunction "COL_8") (pintype "passive"))
    )
    (net (code "24") (name "CH1_B") (class "Default")
      (node (ref "JP1") (pin "2") (pinfunction "2_2") (pintype "passive"))
      (node (ref "OK2") (pin "7") (pinfunction "EMIT_7") (pintype "passive"))
    )
    (net (code "25") (name "CH1_IN") (class "Default")
      (node (ref "IC5") (pin "15") (pinfunction "QA_15") (pintype "tri_state"))
      (node (ref "OK2") (pin "2") (pinfunction "C_2") (pintype "passive"))
    )
    (net (code "26") (name "CH2_A") (class "Default")
      (node (ref "JP1") (pin "3") (pinfunction "3_3") (pintype "passive"))
      (node (ref "OK2") (pin "6") (pinfunction "COL_6") (pintype "passive"))
    )
    (net (code "27") (name "CH2_B") (class "Default")
      (node (ref "JP1") (pin "4") (pinfunction "4_4") (pintype "passive"))
      (node (ref "OK2") (pin "5") (pinfunction "EMIT_5") (pintype "passive"))
    )
    (net (code "28") (name "CH2_IN") (class "Default")
      (node (ref "IC5") (pin "1") (pinfunction "QB_1") (pintype "tri_state"))
      (node (ref "OK2") (pin "4") (pinfunction "C_4") (pintype "passive"))
    )
    (net (code "29") (name "CH3_A") (class "Default")
      (node (ref "JP1") (pin "5") (pinfunction "5_5") (pintype "passive"))
      (node (ref "OK1") (pin "8") (pinfunction "COL_8") (pintype "passive"))
    )
    (net (code "30") (name "CH3_B") (class "Default")
      (node (ref "JP1") (pin "6") (pinfunction "6_6") (pintype "passive"))
      (node (ref "OK1") (pin "7") (pinfunction "EMIT_7") (pintype "passive"))
    )
    (net (code "31") (name "CH3_IN") (class "Default")
      (node (ref "IC5") (pin "2") (pinfunction "QC_2") (pintype "tri_state"))
      (node (ref "OK1") (pin "2") (pinfunction "C_2") (pintype "passive"))
    )
    (net (code "32") (name "CH4_A") (class "Default")
      (node (ref "JP1") (pin "7") (pinfunction "7_7") (pintype "passive"))
      (node (ref "OK1") (pin "6") (pinfunction "COL_6") (pintype "passive"))
    )
    (net (code "33") (name "CH4_B") (class "Default")
      (node (ref "JP1") (pin "8") (pinfunction "8_8") (pintype "passive"))
      (node (ref "OK1") (pin "5") (pinfunction "EMIT_5") (pintype "passive"))
    )
    (net (code "34") (name "CH4_IN") (class "Default")
      (node (ref "IC5") (pin "3") (pinfunction "QD_3") (pintype "tri_state"))
      (node (ref "OK1") (pin "4") (pinfunction "C_4") (pintype "passive"))
    )
    (net (code "35") (name "DC_VOUT") (class "Default")
      (node (ref "DCDC") (pin "VOUT") (pinfunction "VOUT_VOUT") (pintype "bidirectional"))
      (node (ref "PWR") (pin "2") (pinfunction "2_2") (pintype "passive"))
    )
    (net (code "36") (name "DGND") (class "Default")
      (node (ref "ADE-C5") (pin "-") (pinfunction "-_-") (pintype "passive"))
      (node (ref "ANT1") (pin "P$1") (pinfunction "GND_P$1") (pintype "bidirectional"))
      (node (ref "ANT1") (pin "P$2") (pinfunction "GND_P$2") (pintype "bidirectional"))
      (node (ref "ANT2") (pin "P$1") (pinfunction "GND_P$1") (pintype "bidirectional"))
      (node (ref "ANT2") (pin "P$2") (pinfunction "GND_P$2") (pintype "bidirectional"))
      (node (ref "B1") (pin "2") (pinfunction "GND_2") (pintype "bidirectional"))
      (node (ref "B1") (pin "5") (pinfunction "GND_5") (pintype "bidirectional"))
      (node (ref "B1") (pin "6") (pinfunction "GND_6") (pintype "bidirectional"))
      (node (ref "BAT1") (pin "GND") (pinfunction "-_GND") (pintype "power_in"))
      (node (ref "C10") (pin "2") (pinfunction "2_2") (pintype "passive"))
      (node (ref "C20") (pin "2") (pinfunction "2_2") (pintype "passive"))
      (node (ref "C21") (pin "1") (pinfunction "1_1") (pintype "passive"))
      (node (ref "C22") (pin "1") (pinfunction "1_1") (pintype "passive"))
      (node (ref "C23") (pin "1") (pinfunction "1_1") (pintype "passive"))
      (node (ref "C24") (pin "2") (pinfunction "2_2") (pintype "passive"))
      (node (ref "C26") (pin "2") (pinfunction "2_2") (pintype "passive"))
      (node (ref "C27") (pin "2") (pinfunction "2_2") (pintype "passive"))
      (node (ref "C28") (pin "2") (pinfunction "2_2") (pintype "passive"))
      (node (ref "C30") (pin "1") (pinfunction "1_1") (pintype "passive"))
      (node (ref "C31") (pin "2") (pinfunction "2_2") (pintype "passive"))
      (node (ref "C33") (pin "2") (pinfunction "2_2") (pintype "passive"))
      (node (ref "C35") (pin "2") (pinfunction "2_2") (pintype "passive"))
      (node (ref "C36") (pin "1") (pinfunction "1_1") (pintype "passive"))
      (node (ref "C37") (pin "-") (pinfunction "-_-") (pintype "passive"))
      (node (ref "C40") (pin "2") (pinfunction "2_2") (pintype "passive"))
      (node (ref "C41") (pin "2") (pinfunction "2_2") (pintype "passive"))
      (node (ref "C43") (pin "2") (pinfunction "2_2") (pintype "passive"))
      (node (ref "C44") (pin "2") (pinfunction "2_2") (pintype "passive"))
      (node (ref "C45") (pin "2") (pinfunction "2_2") (pintype "passive"))
      (node (ref "C46") (pin "2") (pinfunction "2_2") (pintype "passive"))
      (node (ref "C50") (pin "2") (pinfunction "2_2") (pintype "passive"))
      (node (ref "C51") (pin "2") (pinfunction "2_2") (pintype "passive"))
      (node (ref "C52") (pin "2") (pinfunction "2_2") (pintype "passive"))
      (node (ref "C53") (pin "2") (pinfunction "2_2") (pintype "passive"))
      (node (ref "C54") (pin "2") (pinfunction "2_2") (pintype "passive"))
      (node (ref "C55") (pin "2") (pinfunction "2_2") (pintype "passive"))
      (node (ref "C56") (pin "2") (pinfunction "2_2") (pintype "passive"))
      (node (ref "C57") (pin "2") (pinfunction "2_2") (pintype "passive"))
      (node (ref "C70") (pin "2") (pinfunction "2_2") (pintype "passive"))
      (node (ref "C73") (pin "2") (pinfunction "2_2") (pintype "passive"))
      (node (ref "C74") (pin "2") (pinfunction "2_2") (pintype "passive"))
      (node (ref "C80") (pin "1") (pinfunction "1_1") (pintype "passive"))
      (node (ref "C81") (pin "1") (pinfunction "1_1") (pintype "passive"))
      (node (ref "C96") (pin "-") (pinfunction "-_-") (pintype "passive"))
      (node (ref "C97") (pin "-") (pinfunction "-_-") (pintype "passive"))
      (node (ref "DCDC") (pin "GND$1") (pinfunction "GNDI_GND$1") (pintype "bidirectional"))
      (node (ref "DCDC") (pin "GND$2") (pinfunction "GNDO_GND$2") (pintype "bidirectional"))
      (node (ref "ESP") (pin "GND") (pinfunction "GND_GND") (pintype "bidirectional"))
      (node (ref "ESP") (pin "GPIO15") (pinfunction "GPIO15_GPIO15") (pintype "bidirectional"))
      (node (ref "ESP-C1") (pin "2") (pinfunction "2_2") (pintype "passive"))
      (node (ref "ESP-GPIO0") (pin "3") (pinfunction "3_3") (pintype "passive"))
      (node (ref "HLK-PM01") (pin "GND") (pinfunction "GND_GND") (pintype "bidirectional"))
      (node (ref "IC1") (pin "P$17") (pinfunction "GND_P$17") (pintype "power_in"))
      (node (ref "IC1") (pin "P$18") (pinfunction "GND_P$18") (pintype "power_in"))
      (node (ref "IC1") (pin "P$29") (pinfunction "GND_P$29") (pintype "power_in"))
      (node (ref "IC1") (pin "P$39") (pinfunction "GND_P$39") (pintype "power_in"))
      (node (ref "IC1") (pin "P$45") (pinfunction "GND_P$45") (pintype "power_in"))
      (node (ref "IC1") (pin "P$46") (pinfunction "GND_P$46") (pintype "power_in"))
      (node (ref "IC1") (pin "P$53") (pinfunction "GND_P$53") (pintype "power_in"))
      (node (ref "IC1") (pin "P$54") (pinfunction "GND_P$54") (pintype "power_in"))
      (node (ref "IC1") (pin "P$58") (pinfunction "GND_P$58") (pintype "power_in"))
      (node (ref "IC1") (pin "P$59") (pinfunction "GND_P$59") (pintype "power_in"))
      (node (ref "IC1") (pin "P$61") (pinfunction "GND_P$61") (pintype "power_in"))
      (node (ref "IC1") (pin "P$62") (pinfunction "GND_P$62") (pintype "power_in"))
      (node (ref "IC1") (pin "P$63") (pinfunction "GND_P$63") (pintype "power_in"))
      (node (ref "IC1") (pin "P$64") (pinfunction "GND_P$64") (pintype "power_in"))
      (node (ref "IC1") (pin "P$65") (pinfunction "GND_P$65") (pintype "power_in"))
      (node (ref "IC2") (pin "13") (pinfunction "G_13") (pintype "input"))
      (node (ref "IC2") (pin "8") (pinfunction "GND_8") (pintype "power_in"))
      (node (ref "IC3") (pin "13") (pinfunction "G_13") (pintype "input"))
      (node (ref "IC3") (pin "8") (pinfunction "GND_8") (pintype "power_in"))
      (node (ref "IC4") (pin "2") (pinfunction "DGND_2") (pintype "power_in"))
      (node (ref "IC4") (pin "21") (pinfunction "CS_21") (pintype "input"))
      (node (ref "IC5") (pin "13") (pinfunction "G_13") (pintype "input"))
      (node (ref "IC5") (pin "8") (pinfunction "GND_8") (pintype "power_in"))
      (node (ref "L1") (pin "2") (pinfunction "2_2") (pintype "passive"))
      (node (ref "LCD14") (pin "LCD_GND") (pinfunction "LCD_GND_LCD_GND") (pintype "power_in"))
      (node (ref "LCD14") (pin "T_CS") (pinfunction "T_CS_T_CS") (pintype "bidirectional"))
      (node (ref "LCD_C1") (pin "2") (pinfunction "2_2") (pintype "passive"))
      (node (ref "MQ2-R1") (pin "1") (pinfunction "1_1") (pintype "passive"))
      (node (ref "R31") (pin "1") (pinfunction "1_1") (pintype "passive"))
      (node (ref "R50") (pin "1") (pinfunction "1_1") (pintype "passive"))
      (node (ref "R52") (pin "5") (pinfunction "2_5") (pintype "passive"))
      (node (ref "R52") (pin "6") (pinfunction "2_6") (pintype "passive"))
      (node (ref "R52") (pin "7") (pinfunction "2_7") (pintype "passive"))
      (node (ref "R52") (pin "8") (pinfunction "2_8") (pintype "passive"))
      (node (ref "R53") (pin "1") (pinfunction "1_1") (pintype "passive"))
      (node (ref "R90") (pin "2") (pinfunction "2_2") (pintype "passive"))
      (node (ref "R96") (pin "2") (pinfunction "2_2") (pintype "passive"))
      (node (ref "RBIAS") (pin "2") (pinfunction "2_2") (pintype "passive"))
      (node (ref "RJ-1") (pin "SHIELD$1") (pinfunction "P$5_SHIELD$1") (pintype "bidirectional"))
      (node (ref "RJ-2") (pin "SHIELD$1") (pinfunction "P$5_SHIELD$1") (pintype "bidirectional"))
      (node (ref "RJ-3") (pin "SHIELD$1") (pinfunction "P$5_SHIELD$1") (pintype "bidirectional"))
      (node (ref "S1") (pin "3") (pinfunction "3_3") (pintype "passive"))
      (node (ref "S1") (pin "4") (pinfunction "4_4") (pintype "passive"))
      (node (ref "SENSOR-MQ2") (pin "HB") (pinfunction "HB_HB") (pintype "bidirectional"))
      (node (ref "SIM900-C3") (pin "2") (pinfunction "2_2") (pintype "passive"))
      (node (ref "SIM900-C4") (pin "2") (pinfunction "2_2") (pintype "passive"))
      (node (ref "SIM900-C5") (pin "2") (pinfunction "2_2") (pintype "passive"))
      (node (ref "SIMHOLDER") (pin "SHIELD_GND$1") (pinfunction "GND$1_SHIELD_GND$1") (pintype "bidirectional"))
      (node (ref "SIMHOLDER") (pin "SHIELD_GND$2") (pinfunction "GND$2_SHIELD_GND$2") (pintype "bidirectional"))
      (node (ref "SIMHOLDER") (pin "SIM_GND") (pinfunction "SIM_GND_SIM_GND") (pintype "bidirectional"))
      (node (ref "SR_OUT1") (pin "2") (pinfunction "2_2") (pintype "passive"))
      (node (ref "SR_OUT2") (pin "2") (pinfunction "2_2") (pintype "passive"))
      (node (ref "STM-C13") (pin "2") (pinfunction "2_2") (pintype "passive"))
      (node (ref "STM-SWD") (pin "3") (pinfunction "3_3") (pintype "passive"))
      (node (ref "STM-USART") (pin "4") (pinfunction "4_4") (pintype "passive"))
      (node (ref "STMF401") (pin "18") (pinfunction "VSS_4_18") (pintype "power_in"))
      (node (ref "STMF401") (pin "31") (pinfunction "VSS_1_31") (pintype "power_in"))
      (node (ref "STMF401") (pin "47") (pinfunction "VSS_2_47") (pintype "power_in"))
      (node (ref "STMF401") (pin "63") (pinfunction "VSS_3_63") (pintype "power_in"))
      (node (ref "SYS-C1") (pin "2") (pinfunction "2_2") (pintype "passive"))
      (node (ref "T1") (pin "E") (pinfunction "E_E") (pintype "passive"))
      (node (ref "T2") (pin "E") (pinfunction "E_E") (pintype "passive"))
      (node (ref "T3") (pin "E") (pinfunction "E_E") (pintype "passive"))
      (node (ref "U$17") (pin "GND") (pinfunction "GND_GND") (pintype "bidirectional"))
      (node (ref "U$4") (pin "3") (pinfunction "CS_3") (pintype "input"))
      (node (ref "U2") (pin "14") (pinfunction "AGND_14") (pintype "passive"))
      (node (ref "U2") (pin "16") (pinfunction "AGND_16") (pintype "passive"))
      (node (ref "U2") (pin "19") (pinfunction "AGND_19") (pintype "passive"))
      (node (ref "U2") (pin "29") (pinfunction "GND_29") (pintype "passive"))
      (node (ref "U2") (pin "3") (pinfunction "AGND_3") (pintype "passive"))
      (node (ref "U2") (pin "48") (pinfunction "AGND_48") (pintype "passive"))
      (node (ref "U2") (pin "9") (pinfunction "AGND_9") (pintype "passive"))
      (node (ref "USB_IN") (pin "GND1") (pinfunction "GND_GND1") (pintype "bidirectional"))
      (node (ref "USB_IN") (pin "SHIELD1") (pinfunction "SHIELD_SHIELD1") (pintype "bidirectional"))
      (node (ref "USB_IN") (pin "SHIELD2") (pinfunction "SHIELD_SHIELD2") (pintype "bidirectional"))
      (node (ref "USB_IN") (pin "SHIELD3") (pinfunction "SHIELD_SHIELD3") (pintype "bidirectional"))
      (node (ref "W5500-C13") (pin "-") (pinfunction "-_-") (pintype "passive"))
    )
    (net (code "37") (name "DHT_DATA") (class "Default")
      (node (ref "DHT-R1") (pin "2") (pinfunction "2_2") (pintype "passive"))
      (node (ref "STMF401") (pin "54") (pinfunction "PD2_54") (pintype "bidirectional"))
      (node (ref "U$17") (pin "DATA") (pinfunction "DATA_DATA") (pintype "bidirectional"))
    )
    (net (code "38") (name "ESP_GPIO0") (class "Default")
      (node (ref "ESP") (pin "GPIO00") (pinfunction "GPIO0_GPIO00") (pintype "bidirectional"))
      (node (ref "ESP-GPIO0") (pin "2") (pinfunction "2_2") (pintype "passive"))
    )
    (net (code "39") (name "ESP_RX") (class "Default")
      (node (ref "ESP") (pin "RXD") (pinfunction "RXD_RXD") (pintype "bidirectional"))
      (node (ref "ESP_EXT") (pin "3") (pinfunction "3_3") (pintype "passive"))
      (node (ref "JRX") (pin "1") (pinfunction "1_1") (pintype "passive"))
    )
    (net (code "40") (name "ESP_TX") (class "Default")
      (node (ref "ESP") (pin "TXD") (pinfunction "TXD_TXD") (pintype "bidirectional"))
      (node (ref "ESP_EXT") (pin "4") (pinfunction "4_4") (pintype "passive"))
      (node (ref "JTX") (pin "1") (pinfunction "1_1") (pintype "passive"))
    )
    (net (code "41") (name "ETH_CS") (class "Default")
      (node (ref "R54") (pin "1") (pinfunction "1_1") (pintype "passive"))
      (node (ref "STMF401") (pin "33") (pinfunction "PB12_33") (pintype "bidirectional"))
      (node (ref "U2") (pin "32") (pinfunction "SCS_N_32") (pintype "passive"))
    )
    (net (code "42") (name "ETH_MISO") (class "Default")
      (node (ref "STMF401") (pin "35") (pinfunction "PB14_35") (pintype "bidirectional"))
      (node (ref "U2") (pin "34") (pinfunction "MISO_34") (pintype "passive"))
    )
    (net (code "43") (name "ETH_MOSI") (class "Default")
      (node (ref "STMF401") (pin "36") (pinfunction "PB15_36") (pintype "bidirectional"))
      (node (ref "U2") (pin "35") (pinfunction "MOSI_35") (pintype "passive"))
    )
    (net (code "44") (name "ETH_RSTN") (class "Default")
      (node (ref "R51") (pin "2") (pinfunction "2_2") (pintype "passive"))
      (node (ref "STMF401") (pin "37") (pinfunction "PC6_37") (pintype "bidirectional"))
      (node (ref "U2") (pin "37") (pinfunction "RST_N_37") (pintype "passive"))
    )
    (net (code "45") (name "ETH_SCK") (class "Default")
      (node (ref "STMF401") (pin "34") (pinfunction "PB13_34") (pintype "bidirectional"))
      (node (ref "U2") (pin "33") (pinfunction "SCLK_33") (pintype "passive"))
    )
    (net (code "46") (name "LCD_CS") (class "Default")
      (node (ref "LCD14") (pin "LCD_CS") (pinfunction "LCD_CS_LCD_CS") (pintype "bidirectional"))
      (node (ref "STMF401") (pin "20") (pinfunction "PA4_20") (pintype "bidirectional"))
    )
    (net (code "47") (name "LCD_D{slash}C") (class "Default")
      (node (ref "LCD14") (pin "LCD_D/C") (pinfunction "LCD_D/C_LCD_D/C") (pintype "bidirectional"))
      (node (ref "STMF401") (pin "24") (pinfunction "PC4_24") (pintype "bidirectional"))
    )
    (net (code "48") (name "LCD_LED") (class "Default")
      (node (ref "LCD-R1") (pin "1") (pinfunction "1_1") (pintype "passive"))
      (node (ref "LCD14") (pin "LED") (pinfunction "LCD_LED_LED") (pintype "bidirectional"))
    )
    (net (code "49") (name "LCD_MISO") (class "Default")
      (node (ref "LCD14") (pin "LCD_MISO") (pinfunction "LCD_MISO_LCD_MISO") (pintype "bidirectional"))
      (node (ref "LCD14") (pin "SD_MISO") (pinfunction "SD_MISO_SD_MISO") (pintype "bidirectional"))
      (node (ref "STMF401") (pin "22") (pinfunction "PA6_22") (pintype "bidirectional"))
    )
    (net (code "50") (name "LCD_MOSI") (class "Default")
      (node (ref "LCD14") (pin "LCD_MOSI") (pinfunction "LCD_MOSI_LCD_MOSI") (pintype "bidirectional"))
      (node (ref "LCD14") (pin "SD_MOSI") (pinfunction "SD_MOSI_SD_MOSI") (pintype "bidirectional"))
      (node (ref "STMF401") (pin "23") (pinfunction "PA7_23") (pintype "bidirectional"))
    )
    (net (code "51") (name "LCD_RESET") (class "Default")
      (node (ref "LCD14") (pin "LCD_RESET") (pinfunction "LCD_RESET_LCD_RESET") (pintype "bidirectional"))
      (node (ref "STMF401") (pin "25") (pinfunction "PC5_25") (pintype "bidirectional"))
    )
    (net (code "52") (name "LCD_SCK") (class "Default")
      (node (ref "LCD14") (pin "LCD_SCK") (pinfunction "LCD_SCK_LCD_SCK") (pintype "bidirectional"))
      (node (ref "LCD14") (pin "SD_SCK") (pinfunction "SD_SCK_SD_SCK") (pintype "bidirectional"))
      (node (ref "STMF401") (pin "21") (pinfunction "PA5_21") (pintype "bidirectional"))
    )
    (net (code "53") (name "LINKLED") (class "Default")
      (node (ref "ETH-R5") (pin "1") (pinfunction "1_1") (pintype "passive"))
      (node (ref "U2") (pin "25") (pinfunction "LINKLED_25") (pintype "passive"))
    )
    (net (code "54") (name "MQ2_DATA") (class "Default")
      (node (ref "MQ2-R1") (pin "2") (pinfunction "2_2") (pintype "passive"))
      (node (ref "SENSOR-MQ2") (pin "B1") (pinfunction "B1_B1") (pintype "bidirectional"))
      (node (ref "SENSOR-MQ2") (pin "B2") (pinfunction "B2_B2") (pintype "bidirectional"))
      (node (ref "STMF401") (pin "6") (pinfunction "PH1-_OSC_OUT_6") (pintype "bidirectional"))
    )
    (net (code "55") (name "N") (class "Default")
      (node (ref "HLK-PM01") (pin "AC$2") (pinfunction "AC_IN$2_AC$2") (pintype "bidirectional"))
      (node (ref "TERM_BLOCK") (pin "PIN$4") (pinfunction "P$4_PIN$4") (pintype "bidirectional"))
      (node (ref "TV16-1") (pin "IB") (pinfunction "IB_IB") (pintype "bidirectional"))
      (node (ref "TV16-2") (pin "IB") (pinfunction "IB_IB") (pintype "bidirectional"))
      (node (ref "TV16-3") (pin "IB") (pinfunction "IB_IB") (pintype "bidirectional"))
    )
    (net (code "56") (name "Net-(ADE-R1-Pad1)") (class "Default")
      (node (ref "ADE-R1") (pin "1") (pinfunction "1_1") (pintype "passive"))
      (node (ref "RTO1") (pin "2") (pinfunction "2_2") (pintype "passive"))
      (node (ref "TV16-1") (pin "OA") (pinfunction "OA_OA") (pintype "bidirectional"))
    )
    (net (code "57") (name "Net-(ADE-R2-Pad1)") (class "Default")
      (node (ref "ADE-R2") (pin "1") (pinfunction "1_1") (pintype "passive"))
      (node (ref "RTO2") (pin "2") (pinfunction "2_2") (pintype "passive"))
      (node (ref "TV16-2") (pin "OA") (pinfunction "OA_OA") (pintype "bidirectional"))
    )
    (net (code "58") (name "Net-(ADE-R3-Pad1)") (class "Default")
      (node (ref "ADE-R3") (pin "1") (pinfunction "1_1") (pintype "passive"))
      (node (ref "RTO3") (pin "2") (pinfunction "2_2") (pintype "passive"))
      (node (ref "TV16-3") (pin "OA") (pinfunction "OA_OA") (pintype "bidirectional"))
    )
    (net (code "59") (name "Net-(ADE-R7-Pad1)") (class "Default")
      (node (ref "ADE-R7") (pin "1") (pinfunction "1_1") (pintype "passive"))
      (node (ref "RTO1") (pin "1") (pinfunction "1_1") (pintype "passive"))
      (node (ref "RTO2") (pin "1") (pinfunction "1_1") (pintype "passive"))
      (node (ref "RTO3") (pin "1") (pinfunction "1_1") (pintype "passive"))
      (node (ref "TV16-1") (pin "OB") (pinfunction "OB_OB") (pintype "bidirectional"))
      (node (ref "TV16-2") (pin "OB") (pinfunction "OB_OB") (pintype "bidirectional"))
      (node (ref "TV16-3") (pin "OB") (pinfunction "OB_OB") (pintype "bidirectional"))
    )
    (net (code "60") (name "Net-(ADE-R8-Pad2)") (class "Default")
      (node (ref "ADE-R8") (pin "2") (pinfunction "2_2") (pintype "passive"))
      (node (ref "ADE-R9") (pin "1") (pinfunction "1_1") (pintype "passive"))
      (node (ref "RJ-3") (pin "P$3") (pinfunction "P$3_P$3") (pintype "bidirectional"))
      (node (ref "RJ-3") (pin "P$4") (pinfunction "P$4_P$4") (pintype "bidirectional"))
    )
    (net (code "61") (name "Net-(ADE-R10-Pad1)") (class "Default")
      (node (ref "ADE-R10") (pin "1") (pinfunction "1_1") (pintype "passive"))
      (node (ref "ADE-R8") (pin "1") (pinfunction "1_1") (pintype "passive"))
      (node (ref "RJ-3") (pin "P$1") (pinfunction "P$1_P$1") (pintype "bidirectional"))
      (node (ref "RJ-3") (pin "P$2") (pinfunction "P$2_P$2") (pintype "bidirectional"))
    )
    (net (code "62") (name "Net-(ADE-R11-Pad1)") (class "Default")
      (node (ref "ADE-R11") (pin "1") (pinfunction "1_1") (pintype "passive"))
      (node (ref "ADE-R13") (pin "1") (pinfunction "1_1") (pintype "passive"))
      (node (ref "RJ-2") (pin "P$1") (pinfunction "P$1_P$1") (pintype "bidirectional"))
      (node (ref "RJ-2") (pin "P$2") (pinfunction "P$2_P$2") (pintype "bidirectional"))
    )
    (net (code "63") (name "Net-(ADE-R11-Pad2)") (class "Default")
      (node (ref "ADE-R11") (pin "2") (pinfunction "2_2") (pintype "passive"))
      (node (ref "ADE-R12") (pin "1") (pinfunction "1_1") (pintype "passive"))
      (node (ref "RJ-2") (pin "P$3") (pinfunction "P$3_P$3") (pintype "bidirectional"))
      (node (ref "RJ-2") (pin "P$4") (pinfunction "P$4_P$4") (pintype "bidirectional"))
    )
    (net (code "64") (name "Net-(ADE-R14-Pad1)") (class "Default")
      (node (ref "ADE-R14") (pin "1") (pinfunction "1_1") (pintype "passive"))
      (node (ref "ADE-R16") (pin "1") (pinfunction "1_1") (pintype "passive"))
      (node (ref "RJ-1") (pin "P$1") (pinfunction "P$1_P$1") (pintype "bidirectional"))
      (node (ref "RJ-1") (pin "P$2") (pinfunction "P$2_P$2") (pintype "bidirectional"))
    )
    (net (code "65") (name "Net-(ADE-R14-Pad2)") (class "Default")
      (node (ref "ADE-R14") (pin "2") (pinfunction "2_2") (pintype "passive"))
      (node (ref "ADE-R15") (pin "1") (pinfunction "1_1") (pintype "passive"))
      (node (ref "RJ-1") (pin "P$3") (pinfunction "P$3_P$3") (pintype "bidirectional"))
      (node (ref "RJ-1") (pin "P$4") (pinfunction "P$4_P$4") (pintype "bidirectional"))
    )
    (net (code "66") (name "Net-(ANT1-SIGNAL)") (class "Default")
      (node (ref "ANT1") (pin "P$3") (pinfunction "SIGNAL_P$3") (pintype "bidirectional"))
      (node (ref "IC1") (pin "P$60") (pinfunction "RF_ANT_P$60") (pintype "bidirectional"))
    )
    (net (code "67") (name "Net-(ANT2-SIGNAL)") (class "Default")
      (node (ref "ANT2") (pin "P$3") (pinfunction "SIGNAL_P$3") (pintype "bidirectional"))
      (node (ref "B1") (pin "1") (pinfunction "ANT_1") (pintype "bidirectional"))
    )
    (net (code "68") (name "Net-(B1-BAL_N)") (class "Default")
      (node (ref "B1") (pin "3") (pinfunction "BAL_N_3") (pintype "bidirectional"))
      (node (ref "U$4") (pin "19") (pinfunction "RF-N_19") (pintype "bidirectional"))
    )
    (net (code "69") (name "Net-(B1-BAL_P)") (class "Default")
      (node (ref "B1") (pin "4") (pinfunction "BAL_P_4") (pintype "bidirectional"))
      (node (ref "U$4") (pin "17") (pinfunction "RF-P_17") (pintype "bidirectional"))
    )
    (net (code "70") (name "Net-(ETHERNET-LED1_K)") (class "Default")
      (node (ref "ETH-R4") (pin "2") (pinfunction "2_2") (pintype "passive"))
      (node (ref "ETHERNET") (pin "10") (pinfunction "LED1_K_10") (pintype "bidirectional"))
    )
    (net (code "71") (name "Net-(ETHERNET-LED2_K)") (class "Default")
      (node (ref "ETH-R5") (pin "2") (pinfunction "2_2") (pintype "passive"))
      (node (ref "ETHERNET") (pin "11") (pinfunction "LED2_K_11") (pintype "bidirectional"))
    )
    (net (code "72") (name "Net-(ETHERNET-RCT)") (class "Default")
      (node (ref "C30") (pin "2") (pinfunction "2_2") (pintype "passive"))
      (node (ref "ETHERNET") (pin "6") (pinfunction "RCT_6") (pintype "bidirectional"))
      (node (ref "R30") (pin "1") (pinfunction "1_1") (pintype "passive"))
      (node (ref "R32") (pin "2") (pinfunction "2_2") (pintype "passive"))
    )
    (net (code "73") (name "Net-(ETHERNET-RX+)") (class "Default")
      (node (ref "C32") (pin "1") (pinfunction "1_1") (pintype "passive"))
      (node (ref "ETHERNET") (pin "7") (pinfunction "RX+_7") (pintype "bidirectional"))
    )
    (net (code "74") (name "Net-(ETHERNET-RX-)") (class "Default")
      (node (ref "C34") (pin "1") (pinfunction "1_1") (pintype "passive"))
      (node (ref "ETHERNET") (pin "8") (pinfunction "RX-_8") (pintype "bidirectional"))
    )
    (net (code "75") (name "Net-(ETHERNET-TCT)") (class "Default")
      (node (ref "C36") (pin "2") (pinfunction "2_2") (pintype "passive"))
      (node (ref "ETHERNET") (pin "3") (pinfunction "TCT_3") (pintype "bidirectional"))
      (node (ref "R33") (pin "1") (pinfunction "1_1") (pintype "passive"))
    )
    (net (code "76") (name "Net-(IC1-SIM_CLK)") (class "Default")
      (node (ref "IC1") (pin "P$32") (pinfunction "SIM_CLK_P$32") (pintype "bidirectional"))
      (node (ref "SIM900-R2") (pin "1") (pinfunction "1_1") (pintype "passive"))
    )
    (net (code "77") (name "Net-(IC1-SIM_DATA)") (class "Default")
      (node (ref "IC1") (pin "P$31") (pinfunction "SIM_DATA_P$31") (pintype "bidirectional"))
      (node (ref "SIM900-R3") (pin "1") (pinfunction "1_1") (pintype "passive"))
    )
    (net (code "78") (name "Net-(IC1-SIM_RST)") (class "Default")
      (node (ref "IC1") (pin "P$33") (pinfunction "SIM_RST_P$33") (pintype "bidirectional"))
      (node (ref "SIM900-R1") (pin "1") (pinfunction "1_1") (pintype "passive"))
    )
    (net (code "79") (name "Net-(IC1-VBAT1)") (class "Default")
      (node (ref "C96") (pin "+") (pinfunction "+_+") (pintype "passive"))
      (node (ref "C97") (pin "+") (pinfunction "+_+") (pintype "passive"))
      (node (ref "IC1") (pin "P$55") (pinfunction "VBAT1_P$55") (pintype "power_in"))
      (node (ref "IC1") (pin "P$56") (pinfunction "VBAT2_P$56") (pintype "power_in"))
      (node (ref "IC1") (pin "P$57") (pinfunction "VBAT3_P$57") (pintype "power_in"))
      (node (ref "L2") (pin "1") (pinfunction "1_1") (pintype "passive"))
    )
    (net (code "80") (name "Net-(IC1-VRTC)") (class "Default")
      (node (ref "IC1") (pin "P$26") (pinfunction "VRTC_P$26") (pintype "power_in"))
      (node (ref "SIM900-C3") (pin "1") (pinfunction "1_1") (pintype "passive"))
    )
    (net (code "81") (name "Net-(IC4A-CLKIN)") (class "Default")
      (node (ref "ADE-XTAL") (pin "1") (pinfunction "1_1") (pintype "passive"))
      (node (ref "C73") (pin "1") (pinfunction "1_1") (pintype "passive"))
      (node (ref "IC4") (pin "19") (pinfunction "CLKIN_19") (pintype "input"))
    )
    (net (code "82") (name "Net-(IC4A-CLKOUT)") (class "Default")
      (node (ref "ADE-XTAL") (pin "2") (pinfunction "2_2") (pintype "passive"))
      (node (ref "C74") (pin "1") (pinfunction "1_1") (pintype "passive"))
      (node (ref "IC4") (pin "20") (pinfunction "CLKOUT_20") (pintype "output"))
    )
    (net (code "83") (name "Net-(IC4C-IN)") (class "Default")
      (node (ref "ADE-C12") (pin "1") (pinfunction "1_1") (pintype "passive"))
      (node (ref "ADE-R10") (pin "2") (pinfunction "2_2") (pintype "passive"))
      (node (ref "IC4") (pin "6") (pinfunction "IN_6") (pintype "input"))
    )
    (net (code "84") (name "Net-(IC4C-IP)") (class "Default")
      (node (ref "ADE-C11") (pin "1") (pinfunction "1_1") (pintype "passive"))
      (node (ref "ADE-R9") (pin "2") (pinfunction "2_2") (pintype "passive"))
      (node (ref "IC4") (pin "5") (pinfunction "IP_5") (pintype "input"))
    )
    (net (code "85") (name "Net-(IC4D-IN)") (class "Default")
      (node (ref "ADE-C14") (pin "1") (pinfunction "1_1") (pintype "passive"))
      (node (ref "ADE-R13") (pin "2") (pinfunction "2_2") (pintype "passive"))
      (node (ref "IC4") (pin "8") (pinfunction "IN_8") (pintype "input"))
    )
    (net (code "86") (name "Net-(IC4D-IP)") (class "Default")
      (node (ref "ADE-C13") (pin "1") (pinfunction "1_1") (pintype "passive"))
      (node (ref "ADE-R12") (pin "2") (pinfunction "2_2") (pintype "passive"))
      (node (ref "IC4") (pin "7") (pinfunction "IP_7") (pintype "input"))
    )
    (net (code "87") (name "Net-(IC4E-IN)") (class "Default")
      (node (ref "ADE-C16") (pin "1") (pinfunction "1_1") (pintype "passive"))
      (node (ref "ADE-R16") (pin "2") (pinfunction "2_2") (pintype "passive"))
      (node (ref "IC4") (pin "10") (pinfunction "IN_10") (pintype "input"))
    )
    (net (code "88") (name "Net-(IC4E-IP)") (class "Default")
      (node (ref "ADE-C15") (pin "1") (pinfunction "1_1") (pintype "passive"))
      (node (ref "ADE-R15") (pin "2") (pinfunction "2_2") (pintype "passive"))
      (node (ref "IC4") (pin "9") (pinfunction "IP_9") (pintype "input"))
    )
    (net (code "89") (name "Net-(IC4F-REF)") (class "Default")
      (node (ref "C71") (pin "1") (pinfunction "1_1") (pintype "passive"))
      (node (ref "C72") (pin "1") (pinfunction "1_1") (pintype "passive"))
      (node (ref "IC4") (pin "12") (pinfunction "REF_12") (pintype "bidirectional"))
    )
    (net (code "90") (name "Net-(IC4G-VAP)") (class "Default")
      (node (ref "ADE-C7") (pin "1") (pinfunction "1_1") (pintype "passive"))
      (node (ref "ADE-R1") (pin "2") (pinfunction "2_2") (pintype "passive"))
      (node (ref "ADE-R4") (pin "2") (pinfunction "2_2") (pintype "passive"))
      (node (ref "IC4") (pin "16") (pinfunction "VAP_16") (pintype "input"))
    )
    (net (code "91") (name "Net-(IC4G-VBP)") (class "Default")
      (node (ref "ADE-C8") (pin "1") (pinfunction "1_1") (pintype "passive"))
      (node (ref "ADE-R2") (pin "2") (pinfunction "2_2") (pintype "passive"))
      (node (ref "ADE-R5") (pin "2") (pinfunction "2_2") (pintype "passive"))
      (node (ref "IC4") (pin "15") (pinfunction "VBP_15") (pintype "input"))
    )
    (net (code "92") (name "Net-(IC4G-VCP)") (class "Default")
      (node (ref "ADE-C9") (pin "1") (pinfunction "1_1") (pintype "passive"))
      (node (ref "ADE-R3") (pin "2") (pinfunction "2_2") (pintype "passive"))
      (node (ref "ADE-R6") (pin "2") (pinfunction "2_2") (pintype "passive"))
      (node (ref "IC4") (pin "14") (pinfunction "VCP_14") (pintype "input"))
    )
    (net (code "93") (name "Net-(IC4G-VN)") (class "Default")
      (node (ref "ADE-C10") (pin "1") (pinfunction "1_1") (pintype "passive"))
      (node (ref "ADE-R7") (pin "2") (pinfunction "2_2") (pintype "passive"))
      (node (ref "IC4") (pin "13") (pinfunction "VN_13") (pintype "input"))
    )
    (net (code "94") (name "Net-(LED1-PadA)") (class "Default")
      (node (ref "LED1") (pin "A") (pinfunction "A_A") (pintype "passive"))
      (node (ref "R94") (pin "1") (pinfunction "1_1") (pintype "passive"))
    )
    (net (code "95") (name "Net-(LED1-PadC)") (class "Default")
      (node (ref "LED1") (pin "C") (pinfunction "C_C") (pintype "passive"))
      (node (ref "T1") (pin "C") (pinfunction "C_C") (pintype "passive"))
    )
    (net (code "96") (name "Net-(LED2-PadA)") (class "Default")
      (node (ref "LED2") (pin "A") (pinfunction "A_A") (pintype "passive"))
      (node (ref "R92") (pin "1") (pinfunction "1_1") (pintype "passive"))
    )
    (net (code "97") (name "Net-(LED2-PadC)") (class "Default")
      (node (ref "LED2") (pin "C") (pinfunction "C_C") (pintype "passive"))
      (node (ref "T2") (pin "C") (pinfunction "C_C") (pintype "passive"))
    )
    (net (code "98") (name "Net-(OK1A-A)") (class "Default")
      (node (ref "OK1") (pin "1") (pinfunction "A_1") (pintype "passive"))
      (node (ref "R_CH3") (pin "2") (pinfunction "2_2") (pintype "passive"))
    )
    (net (code "99") (name "Net-(OK1B-A)") (class "Default")
      (node (ref "OK1") (pin "3") (pinfunction "A_3") (pintype "passive"))
      (node (ref "R_CH4") (pin "2") (pinfunction "2_2") (pintype "passive"))
    )
    (net (code "100") (name "Net-(OK2A-A)") (class "Default")
      (node (ref "OK2") (pin "1") (pinfunction "A_1") (pintype "passive"))
      (node (ref "R_CH1") (pin "2") (pinfunction "2_2") (pintype "passive"))
    )
    (net (code "101") (name "Net-(OK2B-A)") (class "Default")
      (node (ref "OK2") (pin "3") (pinfunction "A_3") (pintype "passive"))
      (node (ref "R_CH2") (pin "2") (pinfunction "2_2") (pintype "passive"))
    )
    (net (code "102") (name "Net-(R50-Pad2)") (class "Default")
      (node (ref "R50") (pin "2") (pinfunction "2_2") (pintype "passive"))
      (node (ref "U2") (pin "23") (pinfunction "RSVD_23") (pintype "passive"))
    )
    (net (code "103") (name "Net-(R52-Pad1)") (class "Default")
      (node (ref "R52") (pin "1") (pinfunction "1_1") (pintype "passive"))
      (node (ref "U2") (pin "41") (pinfunction "RSVD_41") (pintype "passive"))
    )
    (net (code "104") (name "Net-(R52B-1)") (class "Default")
      (node (ref "R52") (pin "2") (pinfunction "1_2") (pintype "passive"))
      (node (ref "U2") (pin "40") (pinfunction "RSVD_40") (pintype "passive"))
    )
    (net (code "105") (name "Net-(R52C-1)") (class "Default")
      (node (ref "R52") (pin "3") (pinfunction "1_3") (pintype "passive"))
      (node (ref "U2") (pin "39") (pinfunction "RSVD_39") (pintype "passive"))
    )
    (net (code "106") (name "Net-(R52D-1)") (class "Default")
      (node (ref "R52") (pin "4") (pinfunction "1_4") (pintype "passive"))
      (node (ref "U2") (pin "38") (pinfunction "RSVD_38") (pintype "passive"))
    )
    (net (code "107") (name "Net-(R53A-2)") (class "Default")
      (node (ref "R53") (pin "8") (pinfunction "2_8") (pintype "passive"))
      (node (ref "U2") (pin "42") (pinfunction "RSVD_42") (pintype "passive"))
    )
    (net (code "108") (name "Net-(R53B-2)") (class "Default")
      (node (ref "R53") (pin "7") (pinfunction "2_7") (pintype "passive"))
      (node (ref "U2") (pin "43") (pinfunction "PMODE2_43") (pintype "passive"))
    )
    (net (code "109") (name "Net-(R53C-2)") (class "Default")
      (node (ref "R53") (pin "6") (pinfunction "2_6") (pintype "passive"))
      (node (ref "U2") (pin "44") (pinfunction "PMODE1_44") (pintype "passive"))
    )
    (net (code "110") (name "Net-(R53D-2)") (class "Default")
      (node (ref "R53") (pin "5") (pinfunction "2_5") (pintype "passive"))
      (node (ref "U2") (pin "45") (pinfunction "PMODE0_45") (pintype "passive"))
    )
    (net (code "111") (name "Net-(R90-Pad1)") (class "Default")
      (node (ref "R90") (pin "1") (pinfunction "1_1") (pintype "passive"))
      (node (ref "R91") (pin "1") (pinfunction "1_1") (pintype "passive"))
      (node (ref "T2") (pin "B") (pinfunction "B_B") (pintype "passive"))
    )
    (net (code "112") (name "Net-(R93-Pad2)") (class "Default")
      (node (ref "R93") (pin "2") (pinfunction "2_2") (pintype "passive"))
      (node (ref "T3") (pin "B") (pinfunction "B_B") (pintype "passive"))
    )
    (net (code "113") (name "Net-(R95-Pad1)") (class "Default")
      (node (ref "R95") (pin "1") (pinfunction "1_1") (pintype "passive"))
      (node (ref "R96") (pin "1") (pinfunction "1_1") (pintype "passive"))
      (node (ref "T1") (pin "B") (pinfunction "B_B") (pintype "passive"))
    )
    (net (code "114") (name "Net-(RT1-Pad2)") (class "Default")
      (node (ref "RT1") (pin "2") (pinfunction "2_2") (pintype "passive"))
      (node (ref "TV16-1") (pin "IA") (pinfunction "IA_IA") (pintype "bidirectional"))
    )
    (net (code "115") (name "Net-(RT2-Pad2)") (class "Default")
      (node (ref "RT2") (pin "2") (pinfunction "2_2") (pintype "passive"))
      (node (ref "TV16-2") (pin "IA") (pinfunction "IA_IA") (pintype "bidirectional"))
    )
    (net (code "116") (name "Net-(RT3-Pad2)") (class "Default")
      (node (ref "RT3") (pin "2") (pinfunction "2_2") (pintype "passive"))
      (node (ref "TV16-3") (pin "IA") (pinfunction "IA_IA") (pintype "bidirectional"))
    )
    (net (code "117") (name "Net-(STMF401-PA2)") (class "Default")
      (node (ref "JRX") (pin "2") (pinfunction "2_2") (pintype "passive"))
      (node (ref "STMF401") (pin "16") (pinfunction "PA2_16") (pintype "bidirectional"))
    )
    (net (code "118") (name "Net-(STMF401-PA3)") (class "Default")
      (node (ref "JTX") (pin "2") (pinfunction "2_2") (pintype "passive"))
      (node (ref "STMF401") (pin "17") (pinfunction "PA3_17") (pintype "bidirectional"))
    )
    (net (code "119") (name "Net-(STMF401-PB11)") (class "Default")
      (node (ref "C28") (pin "1") (pinfunction "1_1") (pintype "passive"))
      (node (ref "STMF401") (pin "30") (pinfunction "PB11_30") (pintype "bidirectional"))
    )
    (net (code "120") (name "Net-(STMF401-PC14-OSC32_IN)") (class "Default")
      (node (ref "C22") (pin "2") (pinfunction "2_2") (pintype "passive"))
      (node (ref "STMF401") (pin "3") (pinfunction "PC14-OSC32_IN_3") (pintype "bidirectional"))
      (node (ref "XTAL1") (pin "2") (pinfunction "2_2") (pintype "passive"))
    )
    (net (code "121") (name "Net-(STMF401-PC15-OSC32_OUT)") (class "Default")
      (node (ref "C21") (pin "2") (pinfunction "2_2") (pintype "passive"))
      (node (ref "STMF401") (pin "4") (pinfunction "PC15-OSC32_OUT_4") (pintype "bidirectional"))
      (node (ref "XTAL1") (pin "1") (pinfunction "1_1") (pintype "passive"))
    )
    (net (code "122") (name "Net-(TERM_BLOCK-P$2)") (class "Default")
      (node (ref "RT2") (pin "1") (pinfunction "1_1") (pintype "passive"))
      (node (ref "TERM_BLOCK") (pin "PIN$2") (pinfunction "P$2_PIN$2") (pintype "bidirectional"))
    )
    (net (code "123") (name "Net-(TERM_BLOCK-P$3)") (class "Default")
      (node (ref "RT3") (pin "1") (pinfunction "1_1") (pintype "passive"))
      (node (ref "TERM_BLOCK") (pin "PIN$3") (pinfunction "P$3_PIN$3") (pintype "bidirectional"))
    )
    (net (code "124") (name "Net-(U$4B-DCOUPL)") (class "Default")
      (node (ref "C40") (pin "1") (pinfunction "1_1") (pintype "passive"))
      (node (ref "U$4") (pin "27") (pinfunction "DCOUPL_27") (pintype "power_in"))
    )
    (net (code "125") (name "Net-(U$4C-RBIAS)") (class "Default")
      (node (ref "RBIAS") (pin "1") (pinfunction "1_1") (pintype "passive"))
      (node (ref "U$4") (pin "23") (pinfunction "RBIAS_23") (pintype "bidirectional"))
    )
    (net (code "126") (name "Net-(U$4C-VREG-EN)") (class "Default")
      (node (ref "R_VREG") (pin "1") (pinfunction "1_1") (pintype "passive"))
      (node (ref "U$4") (pin "26") (pinfunction "VREG-EN_26") (pintype "input"))
    )
    (net (code "127") (name "Net-(U$4C-XOSC32M-Q1)") (class "Default")
      (node (ref "C44") (pin "1") (pinfunction "1_1") (pintype "passive"))
      (node (ref "U$4") (pin "13") (pinfunction "XOSC32M-Q1_13") (pintype "input"))
      (node (ref "X1") (pin "1") (pinfunction "1_1") (pintype "bidirectional"))
    )
    (net (code "128") (name "Net-(U$4C-XOSC32M-Q2)") (class "Default")
      (node (ref "C45") (pin "1") (pinfunction "1_1") (pintype "passive"))
      (node (ref "U$4") (pin "12") (pinfunction "XOSC32M-Q2_12") (pintype "output"))
      (node (ref "X1") (pin "3") (pinfunction "2_3") (pintype "bidirectional"))
    )
    (net (code "129") (name "Net-(U2-1V2O)") (class "Default")
      (node (ref "C55") (pin "1") (pinfunction "1_1") (pintype "passive"))
      (node (ref "U2") (pin "22") (pinfunction "1V2O_22") (pintype "passive"))
    )
    (net (code "130") (name "Net-(U2-EXRES1)") (class "Default")
      (node (ref "R31") (pin "2") (pinfunction "2_2") (pintype "passive"))
      (node (ref "U2") (pin "10") (pinfunction "EXRES1_10") (pintype "passive"))
    )
    (net (code "131") (name "Net-(U2-TOCAP)") (class "Default")
      (node (ref "C52") (pin "1") (pinfunction "1_1") (pintype "passive"))
      (node (ref "U2") (pin "20") (pinfunction "TOCAP_20") (pintype "passive"))
    )
    (net (code "132") (name "Net-(U2-XI{slash}CLKIN)") (class "Default")
      (node (ref "C54") (pin "1") (pinfunction "1_1") (pintype "passive"))
      (node (ref "R56") (pin "1") (pinfunction "1_1") (pintype "passive"))
      (node (ref "U2") (pin "30") (pinfunction "XI/CLKIN_30") (pintype "passive"))
      (node (ref "XTAL2") (pin "1") (pinfunction "1_1") (pintype "passive"))
    )
    (net (code "133") (name "Net-(U2-XO)") (class "Default")
      (node (ref "C57") (pin "1") (pinfunction "1_1") (pintype "passive"))
      (node (ref "R56") (pin "2") (pinfunction "2_2") (pintype "passive"))
      (node (ref "U2") (pin "31") (pinfunction "XO_31") (pintype "passive"))
      (node (ref "XTAL2") (pin "2") (pinfunction "2_2") (pintype "passive"))
    )
    (net (code "134") (name "Q1") (class "Default")
      (node (ref "IC2") (pin "15") (pinfunction "QA_15") (pintype "tri_state"))
      (node (ref "SR_OUT1") (pin "3") (pinfunction "3_3") (pintype "passive"))
    )
    (net (code "135") (name "Q2") (class "Default")
      (node (ref "IC2") (pin "1") (pinfunction "QB_1") (pintype "tri_state"))
      (node (ref "SR_OUT1") (pin "4") (pinfunction "4_4") (pintype "passive"))
    )
    (net (code "136") (name "Q3") (class "Default")
      (node (ref "IC2") (pin "2") (pinfunction "QC_2") (pintype "tri_state"))
      (node (ref "SR_OUT1") (pin "5") (pinfunction "5_5") (pintype "passive"))
    )
    (net (code "137") (name "Q4") (class "Default")
      (node (ref "IC2") (pin "3") (pinfunction "QD_3") (pintype "tri_state"))
      (node (ref "SR_OUT1") (pin "6") (pinfunction "6_6") (pintype "passive"))
    )
    (net (code "138") (name "Q5") (class "Default")
      (node (ref "IC2") (pin "4") (pinfunction "QE_4") (pintype "tri_state"))
      (node (ref "SR_OUT1") (pin "7") (pinfunction "7_7") (pintype "passive"))
    )
    (net (code "139") (name "Q6") (class "Default")
      (node (ref "IC2") (pin "5") (pinfunction "QF_5") (pintype "tri_state"))
      (node (ref "SR_OUT1") (pin "8") (pinfunction "8_8") (pintype "passive"))
    )
    (net (code "140") (name "Q7") (class "Default")
      (node (ref "IC2") (pin "6") (pinfunction "QG_6") (pintype "tri_state"))
      (node (ref "SR_OUT1") (pin "9") (pinfunction "9_9") (pintype "passive"))
    )
    (net (code "141") (name "Q8") (class "Default")
      (node (ref "IC2") (pin "7") (pinfunction "QH_7") (pintype "tri_state"))
      (node (ref "SR_OUT1") (pin "10") (pinfunction "10_10") (pintype "passive"))
    )
    (net (code "142") (name "Q9") (class "Default")
      (node (ref "IC3") (pin "15") (pinfunction "QA_15") (pintype "tri_state"))
      (node (ref "SR_OUT2") (pin "3") (pinfunction "3_3") (pintype "passive"))
    )
    (net (code "143") (name "Q10") (class "Default")
      (node (ref "IC3") (pin "1") (pinfunction "QB_1") (pintype "tri_state"))
      (node (ref "SR_OUT2") (pin "4") (pinfunction "4_4") (pintype "passive"))
    )
    (net (code "144") (name "Q11") (class "Default")
      (node (ref "IC3") (pin "2") (pinfunction "QC_2") (pintype "tri_state"))
      (node (ref "SR_OUT2") (pin "5") (pinfunction "5_5") (pintype "passive"))
    )
    (net (code "145") (name "Q12") (class "Default")
      (node (ref "IC3") (pin "3") (pinfunction "QD_3") (pintype "tri_state"))
      (node (ref "SR_OUT2") (pin "6") (pinfunction "6_6") (pintype "passive"))
    )
    (net (code "146") (name "Q13") (class "Default")
      (node (ref "IC3") (pin "4") (pinfunction "QE_4") (pintype "tri_state"))
      (node (ref "SR_OUT2") (pin "7") (pinfunction "7_7") (pintype "passive"))
    )
    (net (code "147") (name "Q14") (class "Default")
      (node (ref "IC3") (pin "5") (pinfunction "QF_5") (pintype "tri_state"))
      (node (ref "SR_OUT2") (pin "8") (pinfunction "8_8") (pintype "passive"))
    )
    (net (code "148") (name "Q15") (class "Default")
      (node (ref "IC3") (pin "6") (pinfunction "QG_6") (pintype "tri_state"))
      (node (ref "SR_OUT2") (pin "9") (pinfunction "9_9") (pintype "passive"))
    )
    (net (code "149") (name "Q16") (class "Default")
      (node (ref "IC3") (pin "7") (pinfunction "QH_7") (pintype "tri_state"))
      (node (ref "SR_OUT2") (pin "10") (pinfunction "10_10") (pintype "passive"))
    )
    (net (code "150") (name "QS") (class "Default")
      (node (ref "IC2") (pin "9") (pinfunction "QH*_9") (pintype "tri_state"))
      (node (ref "IC3") (pin "14") (pinfunction "SER_14") (pintype "input"))
    )
    (net (code "151") (name "QS2") (class "Default")
      (node (ref "IC3") (pin "9") (pinfunction "QH*_9") (pintype "tri_state"))
      (node (ref "IC5") (pin "14") (pinfunction "SER_14") (pintype "input"))
    )
    (net (code "152") (name "R") (class "Default")
      (node (ref "HLK-PM01") (pin "AC$1") (pinfunction "AC_IN$1_AC$1") (pintype "bidirectional"))
      (node (ref "RT1") (pin "1") (pinfunction "1_1") (pintype "passive"))
      (node (ref "TERM_BLOCK") (pin "PIN$1") (pinfunction "P$1_PIN$1") (pintype "bidirectional"))
    )
    (net (code "153") (name "RXN") (class "Default")
      (node (ref "C34") (pin "2") (pinfunction "2_2") (pintype "passive"))
      (node (ref "R32") (pin "1") (pinfunction "1_1") (pintype "passive"))
      (node (ref "U2") (pin "5") (pinfunction "RXN_5") (pintype "passive"))
    )
    (net (code "154") (name "RXP") (class "Default")
      (node (ref "C32") (pin "2") (pinfunction "2_2") (pintype "passive"))
      (node (ref "R30") (pin "2") (pinfunction "2_2") (pintype "passive"))
      (node (ref "U2") (pin "6") (pinfunction "RXP_6") (pintype "passive"))
    )
    (net (code "155") (name "SD_CS") (class "Default")
      (node (ref "LCD14") (pin "SD_CS") (pinfunction "SD_CS_SD_CS") (pintype "bidirectional"))
      (node (ref "STMF401") (pin "55") (pinfunction "PB3_55") (pintype "bidirectional"))
    )
    (net (code "156") (name "SERIAL_RX") (class "Default")
      (node (ref "STM-USART") (pin "3") (pinfunction "3_3") (pintype "passive"))
      (node (ref "STMF401") (pin "43") (pinfunction "PA10_43") (pintype "bidirectional"))
    )
    (net (code "157") (name "SERIAL_TX") (class "Default")
      (node (ref "STM-USART") (pin "2") (pinfunction "2_2") (pintype "passive"))
      (node (ref "STMF401") (pin "42") (pinfunction "PA9_42") (pintype "bidirectional"))
    )
    (net (code "158") (name "SIM900_PWRKEY") (class "Default")
      (node (ref "IC1") (pin "P$1") (pinfunction "PWRKEY_P$1") (pintype "power_in"))
      (node (ref "T3") (pin "C") (pinfunction "C_C") (pintype "passive"))
    )
    (net (code "159") (name "SIM_NETLIGHT") (class "Default")
      (node (ref "IC1") (pin "P$52") (pinfunction "NETLIGHT_P$52") (pintype "bidirectional"))
      (node (ref "R91") (pin "2") (pinfunction "2_2") (pintype "passive"))
    )
    (net (code "160") (name "SIM_PWRKEY") (class "Default")
      (node (ref "R93") (pin "1") (pinfunction "1_1") (pintype "passive"))
      (node (ref "STMF401") (pin "41") (pinfunction "PA8_41") (pintype "bidirectional"))
    )
    (net (code "161") (name "SIM_RX") (class "Default")
      (node (ref "IC1") (pin "P$10") (pinfunction "RXD_P$10") (pintype "input"))
      (node (ref "STMF401") (pin "51") (pinfunction "PC10_51") (pintype "bidirectional"))
    )
    (net (code "162") (name "SIM_STATUS") (class "Default")
      (node (ref "IC1") (pin "P$66") (pinfunction "STATUS_P$66") (pintype "bidirectional"))
      (node (ref "R95") (pin "2") (pinfunction "2_2") (pintype "passive"))
    )
    (net (code "163") (name "SIM_TX") (class "Default")
      (node (ref "IC1") (pin "P$9") (pinfunction "TXD_P$9") (pintype "output"))
      (node (ref "STMF401") (pin "50") (pinfunction "PA15_50") (pintype "bidirectional"))
    )
    (net (code "164") (name "SR_DS") (class "Default")
      (node (ref "IC2") (pin "14") (pinfunction "SER_14") (pintype "input"))
      (node (ref "STMF401") (pin "8") (pinfunction "PC0_8") (pintype "bidirectional"))
    )
    (net (code "165") (name "SR_RST") (class "Default")
      (node (ref "IC2") (pin "10") (pinfunction "SCL_10") (pintype "input"))
      (node (ref "IC3") (pin "10") (pinfunction "SCL_10") (pintype "input"))
      (node (ref "IC5") (pin "10") (pinfunction "SCL_10") (pintype "input"))
      (node (ref "STMF401") (pin "11") (pinfunction "PC3_11") (pintype "bidirectional"))
    )
    (net (code "166") (name "SR_SHCP") (class "Default")
      (node (ref "IC2") (pin "11") (pinfunction "SCK_11") (pintype "input"))
      (node (ref "IC3") (pin "11") (pinfunction "SCK_11") (pintype "input"))
      (node (ref "IC5") (pin "11") (pinfunction "SCK_11") (pintype "input"))
      (node (ref "STMF401") (pin "10") (pinfunction "PC2_10") (pintype "bidirectional"))
    )
    (net (code "167") (name "SR_STCP") (class "Default")
      (node (ref "IC2") (pin "12") (pinfunction "RCK_12") (pintype "input"))
      (node (ref "IC3") (pin "12") (pinfunction "RCK_12") (pintype "input"))
      (node (ref "IC5") (pin "12") (pinfunction "RCK_12") (pintype "input"))
      (node (ref "STMF401") (pin "9") (pinfunction "PC1_9") (pintype "bidirectional"))
    )
    (net (code "168") (name "SWD_NRST") (class "Default")
      (node (ref "C20") (pin "1") (pinfunction "1_1") (pintype "passive"))
      (node (ref "S1") (pin "1") (pinfunction "1_1") (pintype "passive"))
      (node (ref "S1") (pin "2") (pinfunction "2_2") (pintype "passive"))
      (node (ref "STMF401") (pin "7") (pinfunction "NRST_7") (pintype "bidirectional"))
    )
    (net (code "169") (name "SWD_TCK") (class "Default")
      (node (ref "STM-SWD") (pin "2") (pinfunction "2_2") (pintype "passive"))
      (node (ref "STMF401") (pin "49") (pinfunction "PA14_49") (pintype "bidirectional"))
    )
    (net (code "170") (name "SWD_TMS") (class "Default")
      (node (ref "STM-SWD") (pin "4") (pinfunction "4_4") (pintype "passive"))
      (node (ref "STMF401") (pin "46") (pinfunction "PA13_46") (pintype "bidirectional"))
    )
    (net (code "171") (name "TXN") (class "Default")
      (node (ref "ETHERNET") (pin "2") (pinfunction "TX-_2") (pintype "bidirectional"))
      (node (ref "R34") (pin "1") (pinfunction "1_1") (pintype "passive"))
      (node (ref "U2") (pin "1") (pinfunction "TXN_1") (pintype "passive"))
    )
    (net (code "172") (name "TXP") (class "Default")
      (node (ref "ETHERNET") (pin "1") (pinfunction "TX+_1") (pintype "bidirectional"))
      (node (ref "R35") (pin "1") (pinfunction "1_1") (pintype "passive"))
      (node (ref "U2") (pin "2") (pinfunction "TXP_2") (pintype "passive"))
    )
    (net (code "173") (name "T_CLK") (class "Default")
      (node (ref "LCD14") (pin "T_CLK") (pinfunction "T_CLK_T_CLK") (pintype "bidirectional"))
      (node (ref "STMF401") (pin "27") (pinfunction "PB1_27") (pintype "bidirectional"))
    )
    (net (code "174") (name "T_DIN") (class "Default")
      (node (ref "LCD14") (pin "T_DIN") (pinfunction "T_DIN_T_DIN") (pintype "bidirectional"))
      (node (ref "STMF401") (pin "29") (pinfunction "PB10_29") (pintype "bidirectional"))
    )
    (net (code "175") (name "T_DO") (class "Default")
      (node (ref "LCD14") (pin "T_DO") (pinfunction "T_DO_T_DO") (pintype "bidirectional"))
      (node (ref "STMF401") (pin "26") (pinfunction "PB0_26") (pintype "bidirectional"))
    )
    (net (code "176") (name "T_IRQ") (class "Default")
      (node (ref "LCD14") (pin "T_IRQ") (pinfunction "T_IRQ_T_IRQ") (pintype "bidirectional"))
      (node (ref "STMF401") (pin "28") (pinfunction "PB2_28") (pintype "bidirectional"))
    )
    (net (code "177") (name "USB_DM") (class "Default")
      (node (ref "STMF401") (pin "44") (pinfunction "PA11_44") (pintype "bidirectional"))
      (node (ref "USB_IN") (pin "D-1") (pinfunction "D-_D-1") (pintype "bidirectional"))
    )
    (net (code "178") (name "USB_DP") (class "Default")
      (node (ref "STMF401") (pin "45") (pinfunction "PA12_45") (pintype "bidirectional"))
      (node (ref "USB_IN") (pin "D+1") (pinfunction "D+_D+1") (pintype "bidirectional"))
    )
    (net (code "179") (name "USIM_CLK") (class "Default")
      (node (ref "SIM900-R2") (pin "2") (pinfunction "2_2") (pintype "passive"))
      (node (ref "SIMHOLDER") (pin "SIM_CLK") (pinfunction "SIM_CLK_SIM_CLK") (pintype "bidirectional"))
    )
    (net (code "180") (name "USIM_DATA") (class "Default")
      (node (ref "SIM900-R3") (pin "2") (pinfunction "2_2") (pintype "passive"))
      (node (ref "SIMHOLDER") (pin "SIM_IO") (pinfunction "SIM_IO_SIM_IO") (pintype "bidirectional"))
    )
    (net (code "181") (name "USIM_RESET") (class "Default")
      (node (ref "SIM900-R1") (pin "2") (pinfunction "2_2") (pintype "passive"))
      (node (ref "SIMHOLDER") (pin "SIM_RST") (pinfunction "SIM_RST_SIM_RST") (pintype "bidirectional"))
    )
    (net (code "182") (name "USIM_VCC") (class "Default")
      (node (ref "C80") (pin "2") (pinfunction "2_2") (pintype "passive"))
      (node (ref "C81") (pin "2") (pinfunction "2_2") (pintype "passive"))
      (node (ref "IC1") (pin "P$30") (pinfunction "SIM_VDD_P$30") (pintype "power_in"))
      (node (ref "SIM900-C4") (pin "1") (pinfunction "1_1") (pintype "passive"))
      (node (ref "SIM900-C5") (pin "1") (pinfunction "1_1") (pintype "passive"))
      (node (ref "SIMHOLDER") (pin "SIM_VDD") (pinfunction "SIM_VDD_SIM_VDD") (pintype "bidirectional"))
    )
    (net (code "183") (name "VBAT") (class "Default")
      (node (ref "BAT1") (pin "PWR@1") (pinfunction "+_PWR@1") (pintype "power_in"))
      (node (ref "STMF401") (pin "1") (pinfunction "VLCD_1") (pintype "power_in"))
    )
    (net (code "184") (name "VCC") (class "Default")
      (node (ref "C11") (pin "1") (pinfunction "1_1") (pintype "passive"))
      (node (ref "C25") (pin "1") (pinfunction "1_1") (pintype "passive"))
      (node (ref "C31") (pin "1") (pinfunction "1_1") (pintype "passive"))
      (node (ref "C33") (pin "1") (pinfunction "1_1") (pintype "passive"))
      (node (ref "C35") (pin "1") (pinfunction "1_1") (pintype "passive"))
      (node (ref "C37") (pin "+") (pinfunction "+_+") (pintype "passive"))
      (node (ref "C50") (pin "1") (pinfunction "1_1") (pintype "passive"))
      (node (ref "C51") (pin "1") (pinfunction "1_1") (pintype "passive"))
      (node (ref "C53") (pin "1") (pinfunction "1_1") (pintype "passive"))
      (node (ref "L3") (pin "2") (pinfunction "2_2") (pintype "passive"))
      (node (ref "R10") (pin "2") (pinfunction "2_2") (pintype "passive"))
      (node (ref "R33") (pin "2") (pinfunction "2_2") (pintype "passive"))
      (node (ref "R34") (pin "2") (pinfunction "2_2") (pintype "passive"))
      (node (ref "R35") (pin "2") (pinfunction "2_2") (pintype "passive"))
      (node (ref "STMF401") (pin "13") (pinfunction "VDDA_13") (pintype "power_in"))
      (node (ref "U2") (pin "11") (pinfunction "AVDD_11") (pintype "passive"))
      (node (ref "U2") (pin "15") (pinfunction "AVDD_15") (pintype "passive"))
      (node (ref "U2") (pin "17") (pinfunction "AVDD_17") (pintype "passive"))
      (node (ref "U2") (pin "21") (pinfunction "AVDD_21") (pintype "passive"))
      (node (ref "U2") (pin "4") (pinfunction "AVDD_4") (pintype "passive"))
      (node (ref "U2") (pin "8") (pinfunction "AVDD_8") (pintype "passive"))
    )
    (net (code "185") (name "VDD") (class "Default")
      (node (ref "C10") (pin "1") (pinfunction "1_1") (pintype "passive"))
      (node (ref "C23") (pin "2") (pinfunction "2_2") (pintype "passive"))
      (node (ref "C24") (pin "1") (pinfunction "1_1") (pintype "passive"))
      (node (ref "C26") (pin "1") (pinfunction "1_1") (pintype "passive"))
      (node (ref "C27") (pin "1") (pinfunction "1_1") (pintype "passive"))
      (node (ref "C41") (pin "1") (pinfunction "1_1") (pintype "passive"))
      (node (ref "C43") (pin "1") (pinfunction "1_1") (pintype "passive"))
      (node (ref "C46") (pin "1") (pinfunction "1_1") (pintype "passive"))
      (node (ref "C56") (pin "1") (pinfunction "1_1") (pintype "passive"))
      (node (ref "DHT-R1") (pin "1") (pinfunction "1_1") (pintype "passive"))
      (node (ref "ESP_EXT") (pin "1") (pinfunction "1_1") (pintype "passive"))
      (node (ref "ETHERNET") (pin "12") (pinfunction "LED2_A_12") (pintype "bidirectional"))
      (node (ref "ETHERNET") (pin "9") (pinfunction "LED1_A_9") (pintype "bidirectional"))
      (node (ref "IC2") (pin "16") (pinfunction "VCC_16") (pintype "power_in"))
      (node (ref "IC3") (pin "16") (pinfunction "VCC_16") (pintype "power_in"))
      (node (ref "IC5") (pin "16") (pinfunction "VCC_16") (pintype "power_in"))
      (node (ref "L2") (pin "2") (pinfunction "2_2") (pintype "passive"))
      (node (ref "L3") (pin "1") (pinfunction "1_1") (pintype "passive"))
      (node (ref "LCD-R1") (pin "2") (pinfunction "2_2") (pintype "passive"))
      (node (ref "LCD14") (pin "LCD_VCC") (pinfunction "LCD_VCC_LCD_VCC") (pintype "power_in"))
      (node (ref "LCD_C1") (pin "1") (pinfunction "1_1") (pintype "passive"))
      (node (ref "PWR") (pin "1") (pinfunction "1_1") (pintype "passive"))
      (node (ref "R10") (pin "1") (pinfunction "1_1") (pintype "passive"))
      (node (ref "R51") (pin "1") (pinfunction "1_1") (pintype "passive"))
      (node (ref "R53") (pin "2") (pinfunction "1_2") (pintype "passive"))
      (node (ref "R53") (pin "3") (pinfunction "1_3") (pintype "passive"))
      (node (ref "R53") (pin "4") (pinfunction "1_4") (pintype "passive"))
      (node (ref "R54") (pin "2") (pinfunction "2_2") (pintype "passive"))
      (node (ref "R92") (pin "2") (pinfunction "2_2") (pintype "passive"))
      (node (ref "R94") (pin "2") (pinfunction "2_2") (pintype "passive"))
      (node (ref "R_VREG") (pin "2") (pinfunction "2_2") (pintype "passive"))
      (node (ref "STM-C13") (pin "1") (pinfunction "1_1") (pintype "passive"))
      (node (ref "STM-SWD") (pin "1") (pinfunction "1_1") (pintype "passive"))
      (node (ref "STM-USART") (pin "1") (pinfunction "1_1") (pintype "passive"))
      (node (ref "STMF401") (pin "19") (pinfunction "VDD_4_19") (pintype "power_in"))
      (node (ref "STMF401") (pin "32") (pinfunction "VDD_1_32") (pintype "power_in"))
      (node (ref "STMF401") (pin "48") (pinfunction "VDD_2_48") (pintype "power_in"))
      (node (ref "STMF401") (pin "64") (pinfunction "VDD_3_64") (pintype "power_in"))
      (node (ref "U$17") (pin "VCC") (pinfunction "VCC_VCC") (pintype "bidirectional"))
      (node (ref "U$4") (pin "11") (pinfunction "AVDD_11") (pintype "power_in"))
      (node (ref "U$4") (pin "14") (pinfunction "AVDD_14") (pintype "power_in"))
      (node (ref "U$4") (pin "16") (pinfunction "AVDD_16") (pintype "power_in"))
      (node (ref "U$4") (pin "20") (pinfunction "AVDD_20") (pintype "power_in"))
      (node (ref "U$4") (pin "22") (pinfunction "AVDD_22") (pintype "power_in"))
      (node (ref "U$4") (pin "24") (pinfunction "AVDD-GUARD_24") (pintype "power_in"))
      (node (ref "U$4") (pin "8") (pinfunction "DVDD_8") (pintype "power_in"))
      (node (ref "U2") (pin "28") (pinfunction "VDD_28") (pintype "passive"))
      (node (ref "W5500-C13") (pin "+") (pinfunction "+_+") (pintype "passive"))
    )
    (net (code "186") (name "VESP") (class "Default")
      (node (ref "ESP") (pin "CH_PD") (pinfunction "CH_PD_CH_PD") (pintype "bidirectional"))
      (node (ref "ESP") (pin "GPIO02") (pinfunction "GPIO2_GPIO02") (pintype "bidirectional"))
      (node (ref "ESP") (pin "REST") (pinfunction "REST_REST") (pintype "bidirectional"))
      (node (ref "ESP") (pin "VCC") (pinfunction "VCC_VCC") (pintype "power_in"))
      (node (ref "ESP-C1") (pin "1") (pinfunction "1_1") (pintype "passive"))
      (node (ref "ESP-GPIO0") (pin "1") (pinfunction "1_1") (pintype "passive"))
      (node (ref "ESP_EXT") (pin "2") (pinfunction "2_2") (pintype "passive"))
    )
    (net (code "187") (name "unconnected-(ESP-GPIO4-PadGPIO04)") (class "Default")
      (node (ref "ESP") (pin "GPIO04") (pinfunction "GPIO4_GPIO04") (pintype "bidirectional"))
    )
    (net (code "188") (name "unconnected-(ESP-GPIO5-PadGPIO05)") (class "Default")
      (node (ref "ESP") (pin "GPIO05") (pinfunction "GPIO5_GPIO05") (pintype "bidirectional"))
    )
    (net (code "189") (name "unconnected-(ESP-PadADC)") (class "Default")
      (node (ref "ESP") (pin "ADC") (pinfunction "ADC_ADC") (pintype "bidirectional"))
    )
    (net (code "190") (name "unconnected-(ESP-PadGPIO12)") (class "Default")
      (node (ref "ESP") (pin "GPIO12") (pinfunction "GPIO12_GPIO12") (pintype "bidirectional"))
    )
    (net (code "191") (name "unconnected-(ESP-PadGPIO13)") (class "Default")
      (node (ref "ESP") (pin "GPIO13") (pinfunction "GPIO13_GPIO13") (pintype "bidirectional"))
    )
    (net (code "192") (name "unconnected-(ESP-PadGPIO14)") (class "Default")
      (node (ref "ESP") (pin "GPIO14") (pinfunction "GPIO14_GPIO14") (pintype "bidirectional"))
    )
    (net (code "193") (name "unconnected-(ESP-PadGPIO16)") (class "Default")
      (node (ref "ESP") (pin "GPIO16") (pinfunction "GPIO16_GPIO16") (pintype "bidirectional"))
    )
    (net (code "194") (name "unconnected-(IC1-ADC-PadP$25)") (class "Default")
      (node (ref "IC1") (pin "P$25") (pinfunction "ADC_P$25") (pintype "bidirectional"))
    )
    (net (code "195") (name "unconnected-(IC1-CTS-PadP$7)") (class "Default")
      (node (ref "IC1") (pin "P$7") (pinfunction "CTS_P$7") (pintype "output"))
    )
    (net (code "196") (name "unconnected-(IC1-DBG_RXD-PadP$28)") (class "Default")
      (node (ref "IC1") (pin "P$28") (pinfunction "DBG_RXD_P$28") (pintype "input"))
    )
    (net (code "197") (name "unconnected-(IC1-DBG_TXD-PadP$27)") (class "Default")
      (node (ref "IC1") (pin "P$27") (pinfunction "DBG_TXD_P$27") (pintype "output"))
    )
    (net (code "198") (name "unconnected-(IC1-DCD-PadP$5)") (class "Default")
      (node (ref "IC1") (pin "P$5") (pinfunction "DCD_P$5") (pintype "output"))
    )
    (net (code "199") (name "unconnected-(IC1-DISP_CLK-PadP$11)") (class "Default")
      (node (ref "IC1") (pin "P$11") (pinfunction "DISP_CLK_P$11") (pintype "bidirectional"))
    )
    (net (code "200") (name "unconnected-(IC1-DISP_CS-PadP$14)") (class "Default")
      (node (ref "IC1") (pin "P$14") (pinfunction "DISP_CS_P$14") (pintype "bidirectional"))
    )
    (net (code "201") (name "unconnected-(IC1-DISP_DATA-PadP$12)") (class "Default")
      (node (ref "IC1") (pin "P$12") (pinfunction "DISP_DATA_P$12") (pintype "bidirectional"))
    )
    (net (code "202") (name "unconnected-(IC1-DISP_DC-PadP$13)") (class "Default")
      (node (ref "IC1") (pin "P$13") (pinfunction "DISP_DC_P$13") (pintype "bidirectional"))
    )
    (net (code "203") (name "unconnected-(IC1-DTR-PadP$3)") (class "Default")
      (node (ref "IC1") (pin "P$3") (pinfunction "DTR_P$3") (pintype "input"))
    )
    (net (code "204") (name "unconnected-(IC1-GPIO1{slash}KBR4-PadP$40)") (class "Default")
      (node (ref "IC1") (pin "P$40") (pinfunction "GPIO1/KBR4_P$40") (pintype "bidirectional"))
    )
    (net (code "205") (name "unconnected-(IC1-GPIO2{slash}KBR3-PadP$41)") (class "Default")
      (node (ref "IC1") (pin "P$41") (pinfunction "GPIO2/KBR3_P$41") (pintype "bidirectional"))
    )
    (net (code "206") (name "unconnected-(IC1-GPIO3{slash}KBR2-PadP$42)") (class "Default")
      (node (ref "IC1") (pin "P$42") (pinfunction "GPIO3/KBR2_P$42") (pintype "bidirectional"))
    )
    (net (code "207") (name "unconnected-(IC1-GPIO4{slash}KBR1-PadP$43)") (class "Default")
      (node (ref "IC1") (pin "P$43") (pinfunction "GPIO4/KBR1_P$43") (pintype "bidirectional"))
    )
    (net (code "208") (name "unconnected-(IC1-GPIO5{slash}KBR0-PadP$44)") (class "Default")
      (node (ref "IC1") (pin "P$44") (pinfunction "GPIO5/KBR0_P$44") (pintype "bidirectional"))
    )
    (net (code "209") (name "unconnected-(IC1-GPIO6{slash}KBC4-PadP$47)") (class "Default")
      (node (ref "IC1") (pin "P$47") (pinfunction "GPIO6/KBC4_P$47") (pintype "bidirectional"))
    )
    (net (code "210") (name "unconnected-(IC1-GPIO7{slash}KBC3-PadP$48)") (class "Default")
      (node (ref "IC1") (pin "P$48") (pinfunction "GPIO7/KBC3_P$48") (pintype "bidirectional"))
    )
    (net (code "211") (name "unconnected-(IC1-GPIO8{slash}KBC2-PadP$49)") (class "Default")
      (node (ref "IC1") (pin "P$49") (pinfunction "GPIO8/KBC2_P$49") (pintype "bidirectional"))
    )
    (net (code "212") (name "unconnected-(IC1-GPIO9{slash}KBC1-PadP$50)") (class "Default")
      (node (ref "IC1") (pin "P$50") (pinfunction "GPIO9/KBC1_P$50") (pintype "bidirectional"))
    )
    (net (code "213") (name "unconnected-(IC1-GPIO10-PadP$51)") (class "Default")
      (node (ref "IC1") (pin "P$51") (pinfunction "GPIO10_P$51") (pintype "bidirectional"))
    )
    (net (code "214") (name "unconnected-(IC1-LINEIN_L-PadP$24)") (class "Default")
      (node (ref "IC1") (pin "P$24") (pinfunction "LINEIN_L_P$24") (pintype "bidirectional"))
    )
    (net (code "215") (name "unconnected-(IC1-LINEIN_R-PadP$23)") (class "Default")
      (node (ref "IC1") (pin "P$23") (pinfunction "LINEIN_R_P$23") (pintype "bidirectional"))
    )
    (net (code "216") (name "unconnected-(IC1-MIC_N-PadP$20)") (class "Default")
      (node (ref "IC1") (pin "P$20") (pinfunction "MIC_N_P$20") (pintype "bidirectional"))
    )
    (net (code "217") (name "unconnected-(IC1-MIC_P-PadP$19)") (class "Default")
      (node (ref "IC1") (pin "P$19") (pinfunction "MIC_P_P$19") (pintype "bidirectional"))
    )
    (net (code "218") (name "unconnected-(IC1-NC-PadP$2)") (class "Default")
      (node (ref "IC1") (pin "P$2") (pinfunction "NC_P$2") (pintype "no_connect"))
    )
    (net (code "219") (name "unconnected-(IC1-NC-PadP$6)") (class "Default")
      (node (ref "IC1") (pin "P$6") (pinfunction "NC_P$6") (pintype "no_connect"))
    )
    (net (code "220") (name "unconnected-(IC1-NRESET-PadP$16)") (class "Default")
      (node (ref "IC1") (pin "P$16") (pinfunction "NRESET_P$16") (pintype "bidirectional"))
    )
    (net (code "221") (name "unconnected-(IC1-PWM1-PadP$35)") (class "Default")
      (node (ref "IC1") (pin "P$35") (pinfunction "PWM1_P$35") (pintype "bidirectional"))
    )
    (net (code "222") (name "unconnected-(IC1-PWM2-PadP$36)") (class "Default")
      (node (ref "IC1") (pin "P$36") (pinfunction "PWM2_P$36") (pintype "bidirectional"))
    )
    (net (code "223") (name "unconnected-(IC1-RI-PadP$4)") (class "Default")
      (node (ref "IC1") (pin "P$4") (pinfunction "RI_P$4") (pintype "output"))
    )
    (net (code "224") (name "unconnected-(IC1-RTS-PadP$8)") (class "Default")
      (node (ref "IC1") (pin "P$8") (pinfunction "RTS_P$8") (pintype "input"))
    )
    (net (code "225") (name "unconnected-(IC1-SCL-PadP$38)") (class "Default")
      (node (ref "IC1") (pin "P$38") (pinfunction "SCL_P$38") (pintype "bidirectional"))
    )
    (net (code "226") (name "unconnected-(IC1-SDA-PadP$37)") (class "Default")
      (node (ref "IC1") (pin "P$37") (pinfunction "SDA_P$37") (pintype "bidirectional"))
    )
    (net (code "227") (name "unconnected-(IC1-SIM_PRESENCE-PadP$34)") (class "Default")
      (node (ref "IC1") (pin "P$34") (pinfunction "SIM_PRESENCE_P$34") (pintype "bidirectional"))
    )
    (net (code "228") (name "unconnected-(IC1-SPK_N-PadP$22)") (class "Default")
      (node (ref "IC1") (pin "P$22") (pinfunction "SPK_N_P$22") (pintype "bidirectional"))
    )
    (net (code "229") (name "unconnected-(IC1-SPK_P-PadP$21)") (class "Default")
      (node (ref "IC1") (pin "P$21") (pinfunction "SPK_P_P$21") (pintype "bidirectional"))
    )
    (net (code "230") (name "unconnected-(IC1-VDD_EXT-PadP$15)") (class "Default")
      (node (ref "IC1") (pin "P$15") (pinfunction "VDD_EXT_P$15") (pintype "bidirectional"))
    )
    (net (code "231") (name "unconnected-(IC5A-QE-Pad4)") (class "Default")
      (node (ref "IC5") (pin "4") (pinfunction "QE_4") (pintype "tri_state"))
    )
    (net (code "232") (name "unconnected-(IC5A-QF-Pad5)") (class "Default")
      (node (ref "IC5") (pin "5") (pinfunction "QF_5") (pintype "tri_state"))
    )
    (net (code "233") (name "unconnected-(IC5A-QG-Pad6)") (class "Default")
      (node (ref "IC5") (pin "6") (pinfunction "QG_6") (pintype "tri_state"))
    )
    (net (code "234") (name "unconnected-(IC5A-QH*-Pad9)") (class "Default")
      (node (ref "IC5") (pin "9") (pinfunction "QH*_9") (pintype "tri_state"))
    )
    (net (code "235") (name "unconnected-(IC5A-QH-Pad7)") (class "Default")
      (node (ref "IC5") (pin "7") (pinfunction "QH_7") (pintype "tri_state"))
    )
    (net (code "236") (name "unconnected-(SIMHOLDER-PadVPP)") (class "Default")
      (node (ref "SIMHOLDER") (pin "VPP") (pinfunction "VPP_VPP") (pintype "bidirectional"))
    )
    (net (code "237") (name "unconnected-(STMF401-BOOT0-Pad60)") (class "Default")
      (node (ref "STMF401") (pin "60") (pinfunction "BOOT0_60") (pintype "input"))
    )
    (net (code "238") (name "unconnected-(U$17-PadNO)") (class "Default")
      (node (ref "U$17") (pin "NO") (pinfunction "NO_NO") (pintype "bidirectional"))
    )
    (net (code "239") (name "unconnected-(U2-DNC-Pad7)") (class "Default")
      (node (ref "U2") (pin "7") (pinfunction "DNC_7") (pintype "passive"))
    )
    (net (code "240") (name "unconnected-(U2-DUPLED-Pad26)") (class "Default")
      (node (ref "U2") (pin "26") (pinfunction "DUPLED_26") (pintype "passive"))
    )
    (net (code "241") (name "unconnected-(U2-INT_N-Pad36)") (class "Default")
      (node (ref "U2") (pin "36") (pinfunction "INT_N_36") (pintype "passive"))
    )
    (net (code "242") (name "unconnected-(U2-NC-Pad12)") (class "Default")
      (node (ref "U2") (pin "12") (pinfunction "NC_12") (pintype "passive"))
    )
    (net (code "243") (name "unconnected-(U2-NC-Pad13)") (class "Default")
      (node (ref "U2") (pin "13") (pinfunction "NC_13") (pintype "passive"))
    )
    (net (code "244") (name "unconnected-(U2-NC-Pad46)") (class "Default")
      (node (ref "U2") (pin "46") (pinfunction "NC_46") (pintype "passive"))
    )
    (net (code "245") (name "unconnected-(U2-NC-Pad47)") (class "Default")
      (node (ref "U2") (pin "47") (pinfunction "NC_47") (pintype "passive"))
    )
    (net (code "246") (name "unconnected-(U2-SPDLED-Pad24)") (class "Default")
      (node (ref "U2") (pin "24") (pinfunction "SPDLED_24") (pintype "passive"))
    )
    (net (code "247") (name "unconnected-(U2-VBG-Pad18)") (class "Default")
      (node (ref "U2") (pin "18") (pinfunction "VBG_18") (pintype "passive"))
    )
    (net (code "248") (name "unconnected-(USB_IN-ID-PadID1)") (class "Default")
      (node (ref "USB_IN") (pin "ID1") (pinfunction "ID_ID1") (pintype "bidirectional"))
    )
  )
)
